# FPGA_IO.net
KiCad netlist of a schematic drawn in Altium Designer
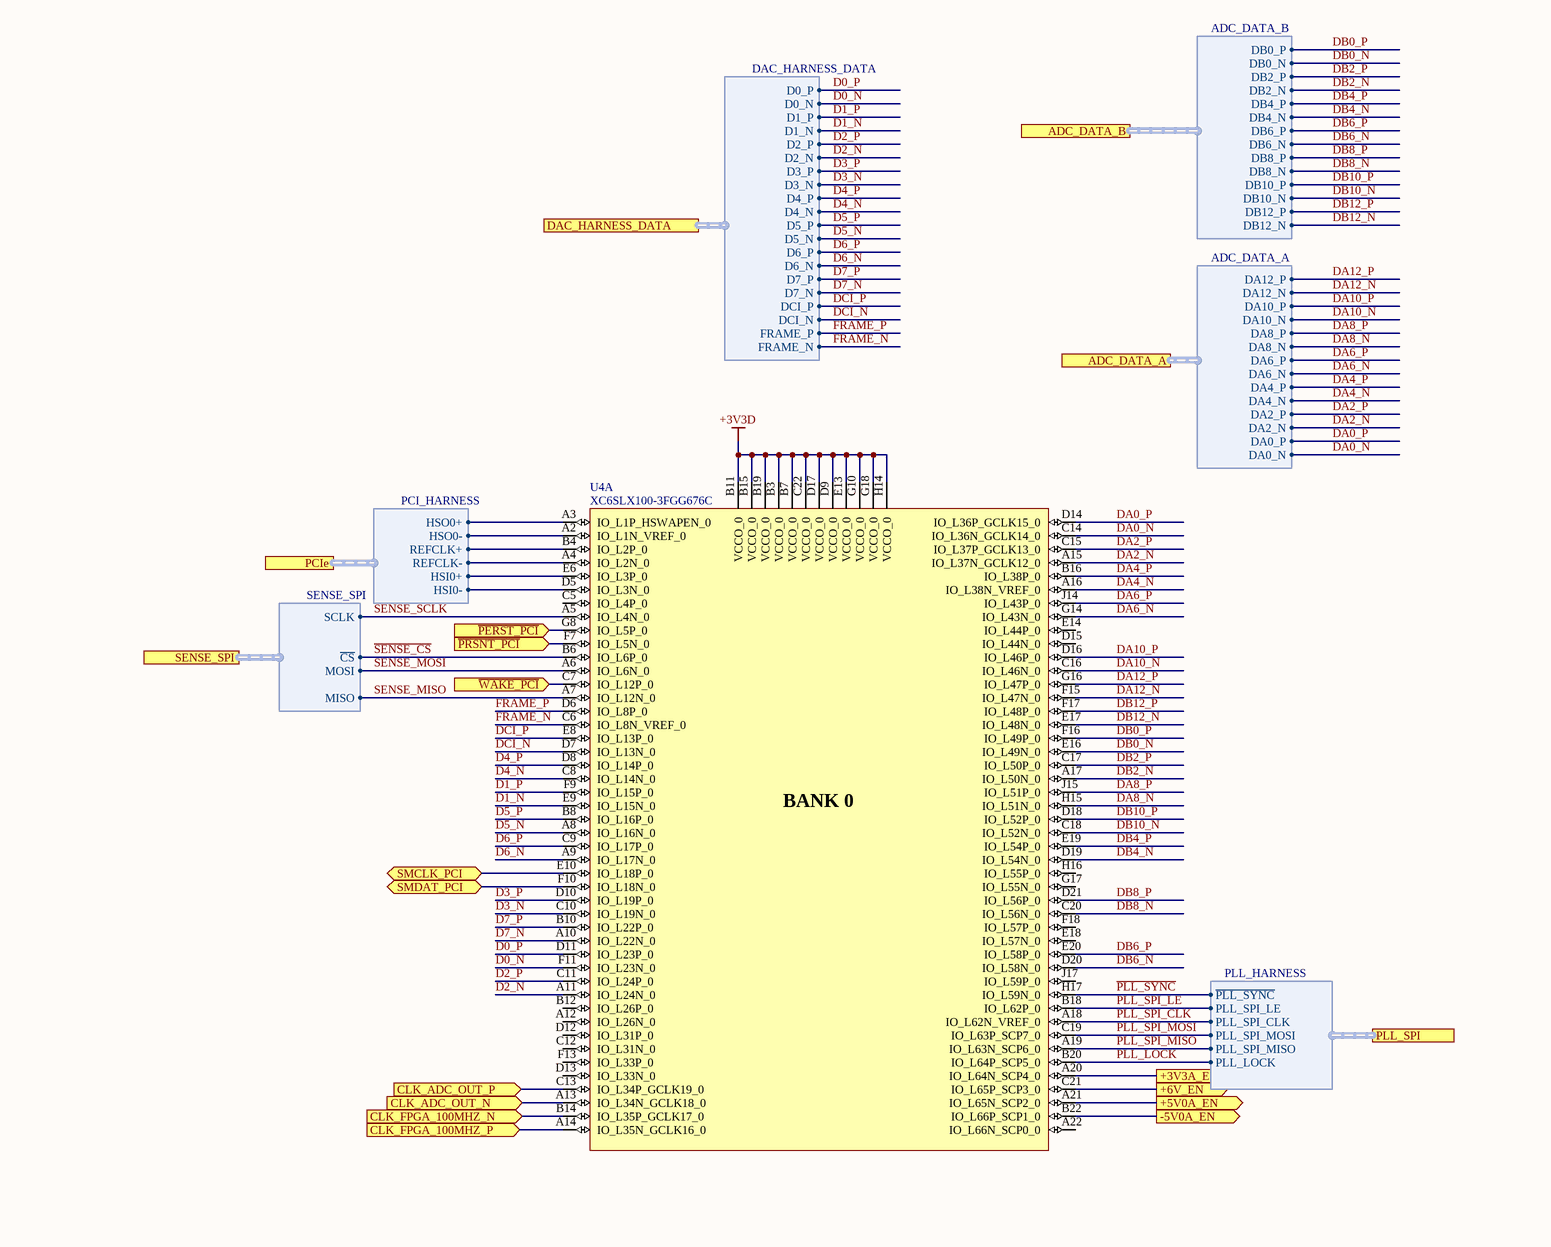
[diagram p0: FPGA_IO.SchDoc, top left]
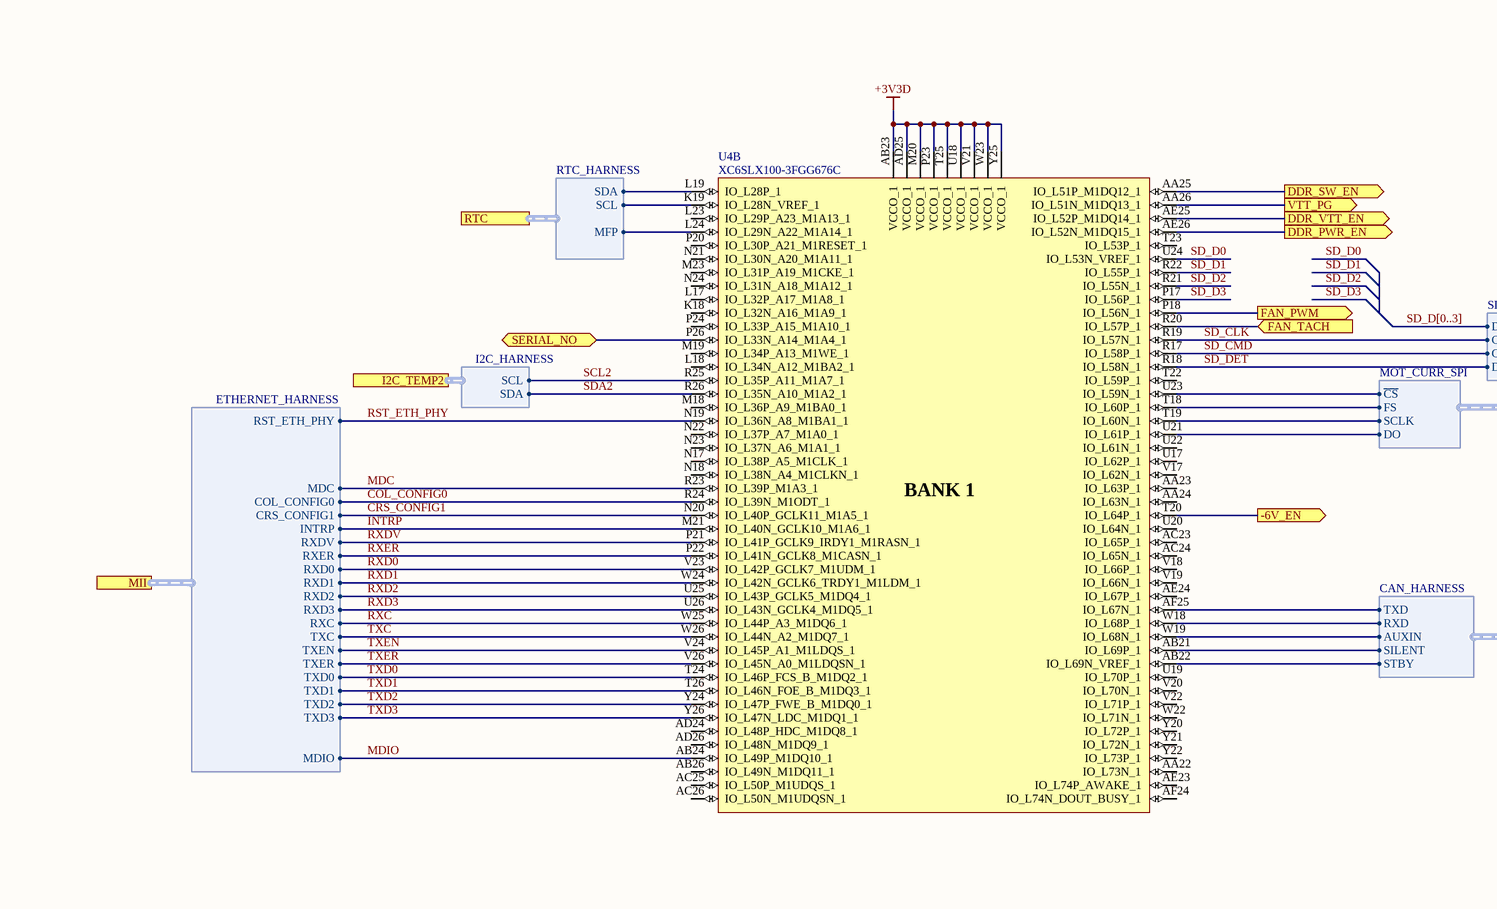
[diagram p1: FPGA_IO.SchDoc, top middle]
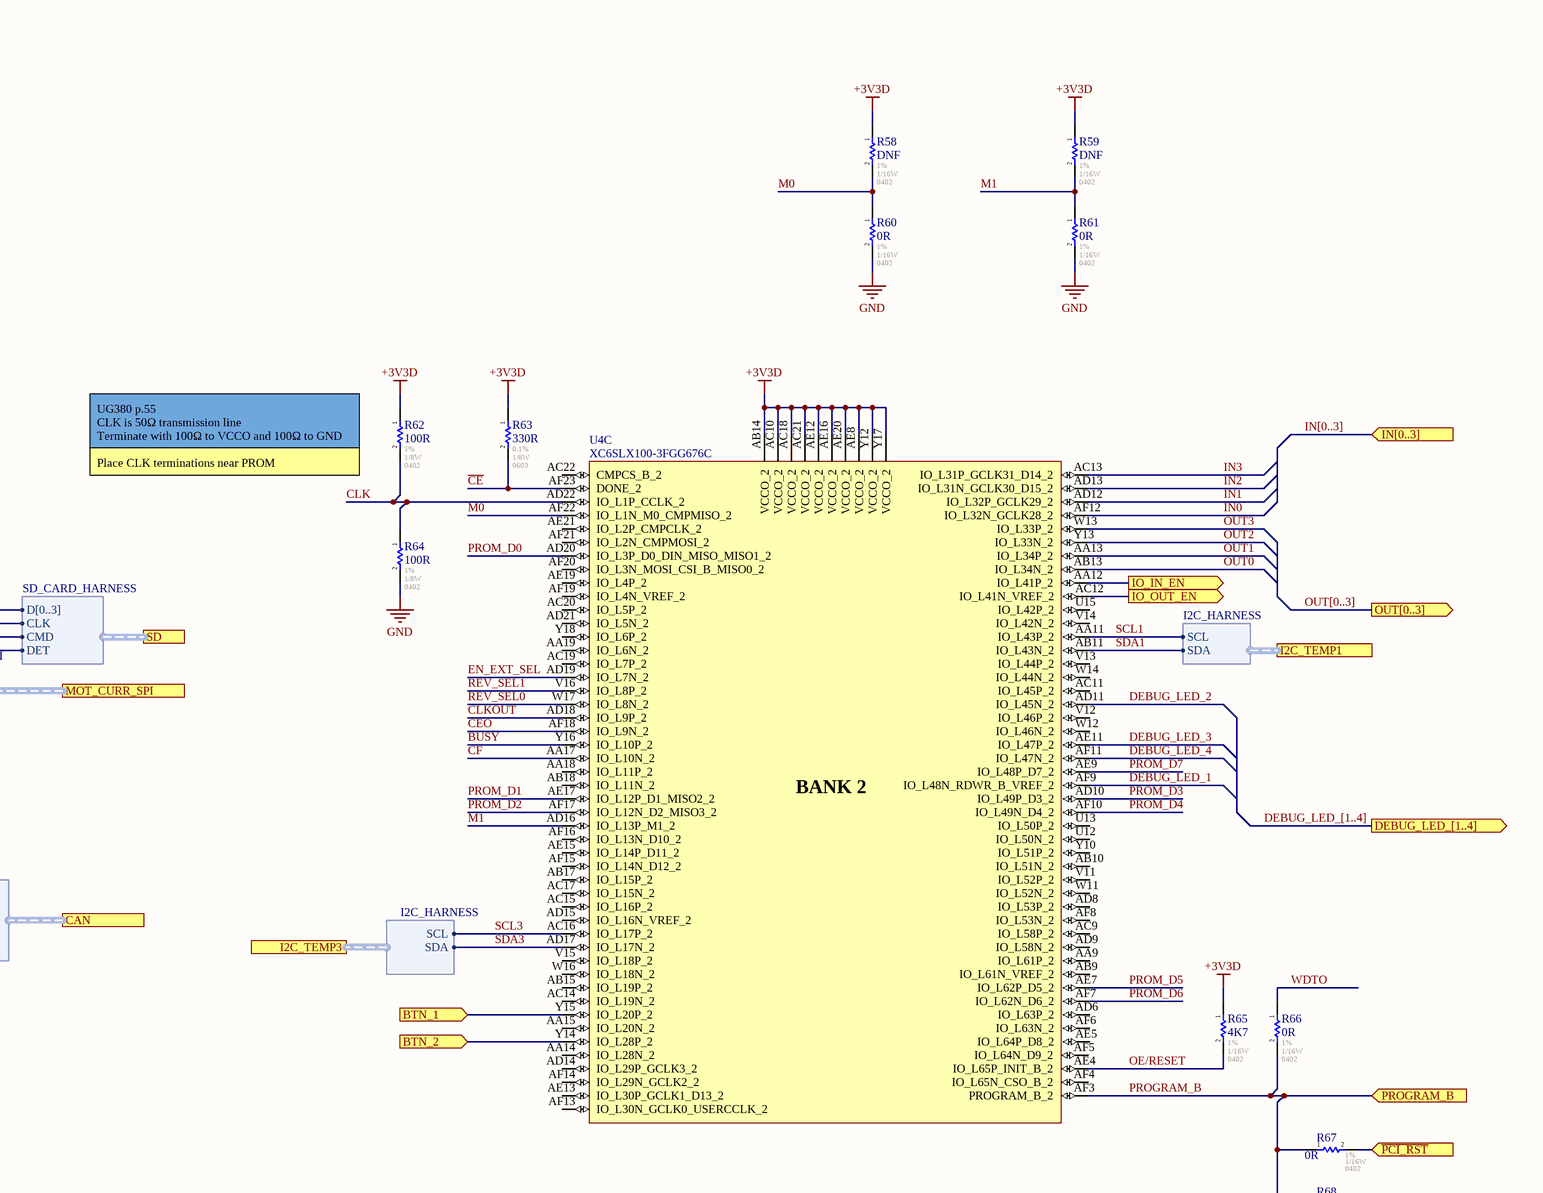
[diagram p2: FPGA_IO.SchDoc, top right]
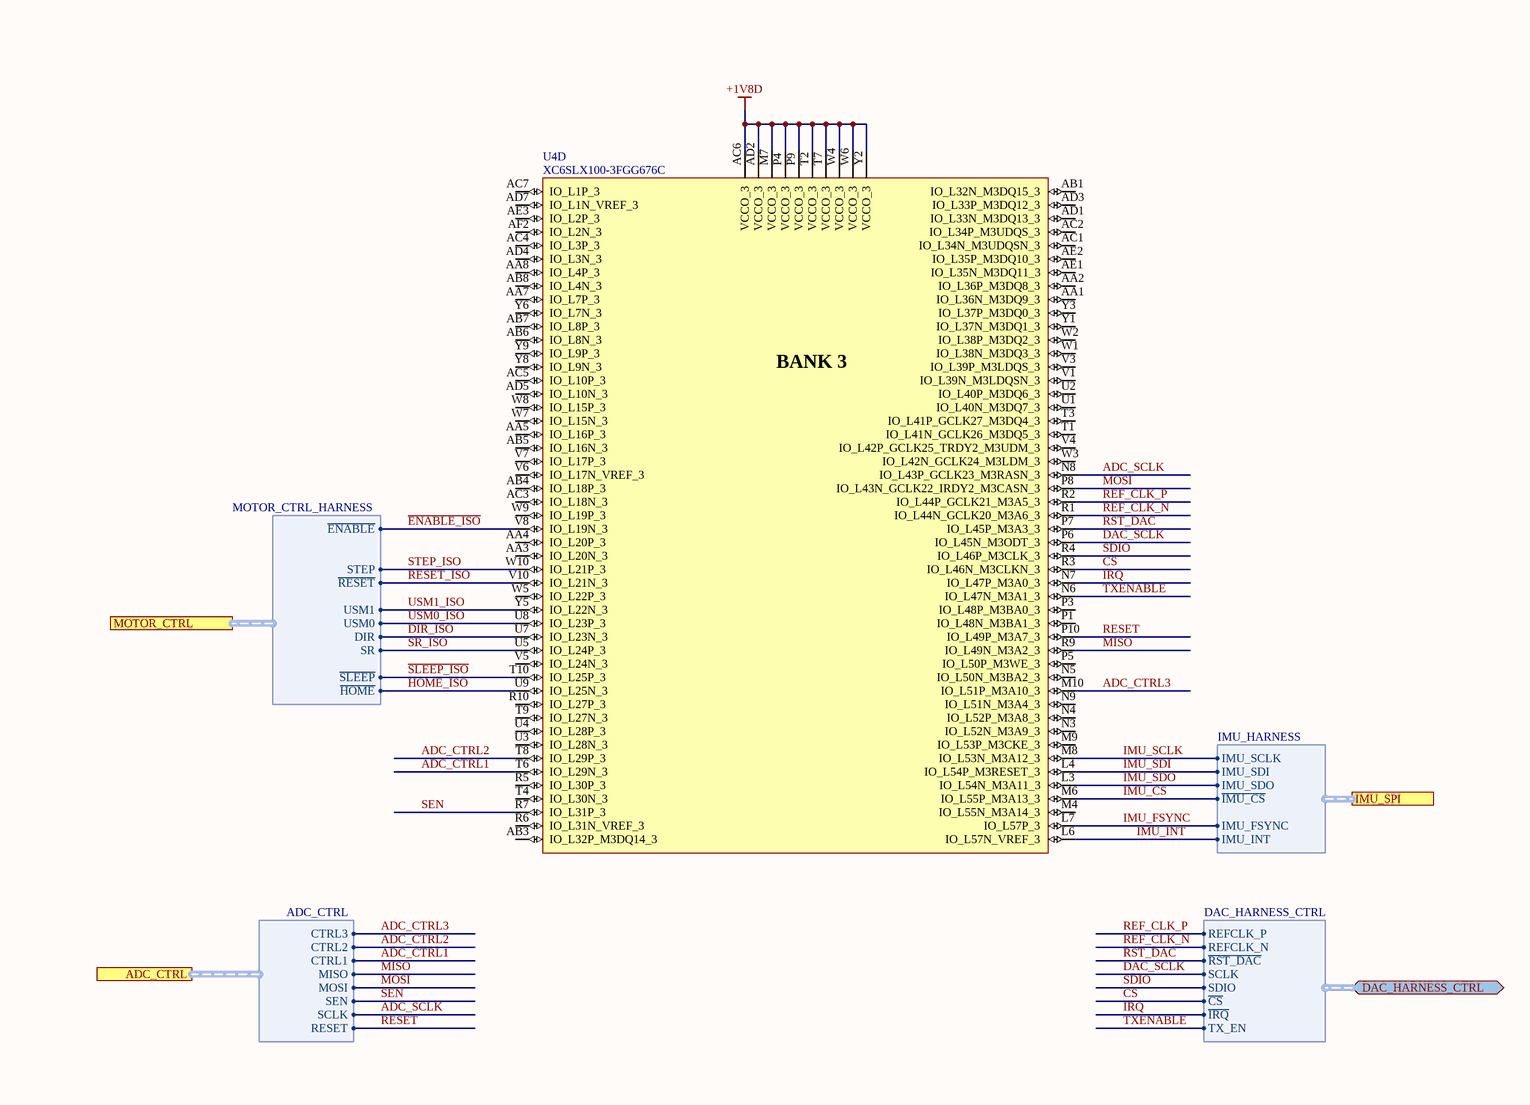
[diagram p3: FPGA_IO.SchDoc, bottom left]
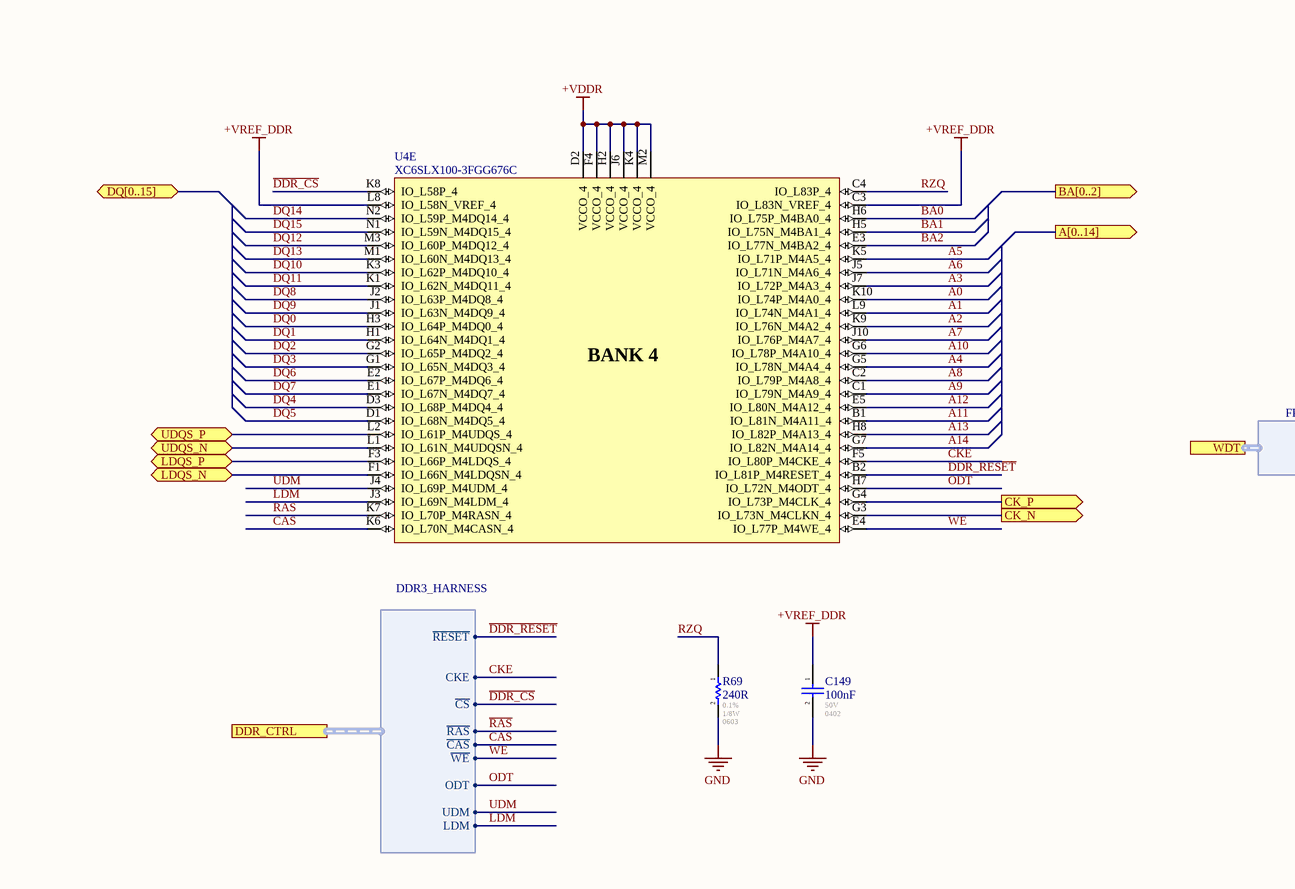
[diagram p4: FPGA_IO.SchDoc, bottom middle]
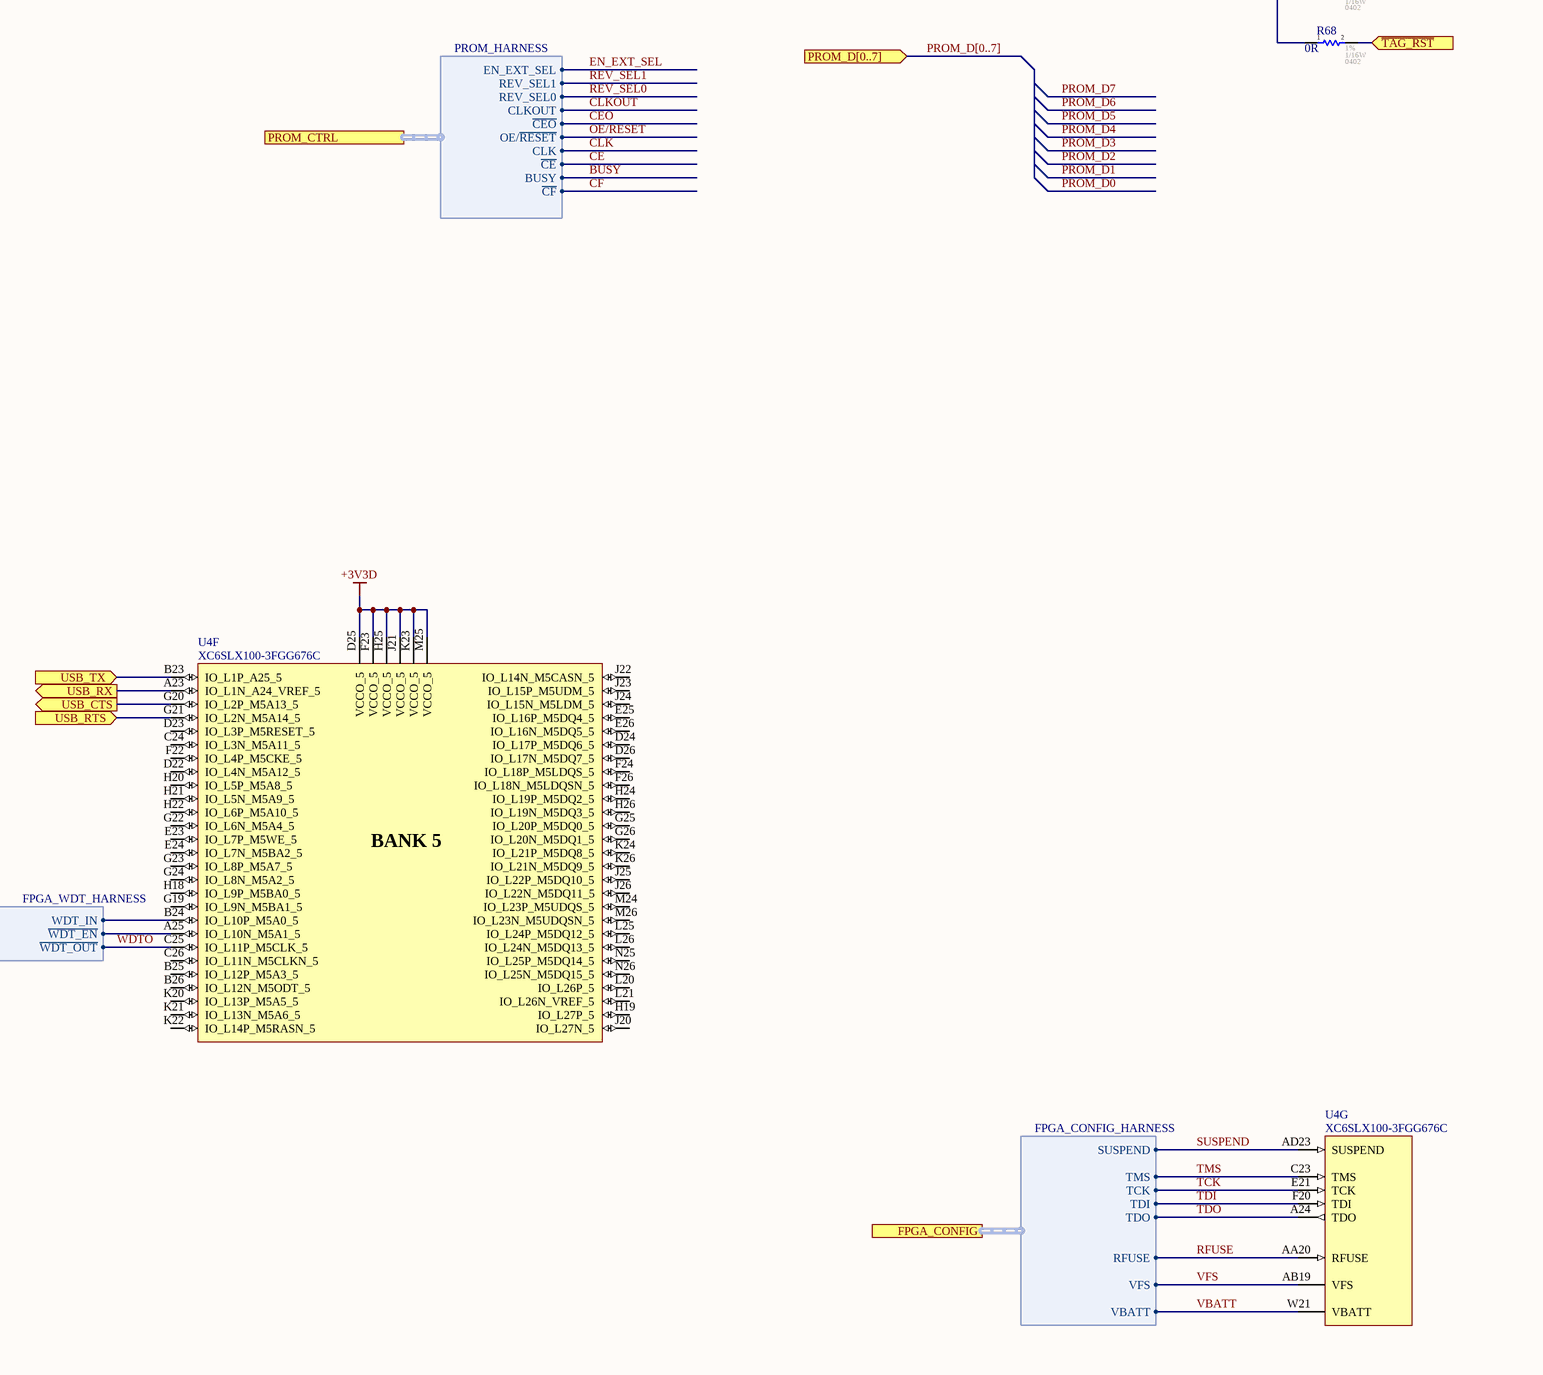
[diagram p5: FPGA_IO.SchDoc, bottom right]

(export (version "E")
  (design (tool "Eeschema 10.0.6"))
  (components
    (comp (ref "C149")
      (value "100nF")
      (footprint "0402")
      (description "GCM155R71H104KE02J\r\n0402 100nF 10% X7R Ceramic Capacitor")
      (fields
        (field (name "MFR") "Murata")
        (field (name "PART#") "GCM155R71H104KE02J")
        (field (name "VOLTAGE - RATED") "50V")
      )
      (libsource (lib "Symbols") (part "CAP_CER"))
    )
    (comp (ref "R58")
      (value "DNF")
      (footprint "RES_0402")
      (fields
        (field (name "TOLERANCE") "1%")
        (field (name "POWER") "1/16W")
        (field (name "PACKAGE / CASE") "0402")
      )
      (libsource (lib "Symbols") (part "RESISTOR"))
    )
    (comp (ref "R59")
      (value "DNF")
      (footprint "RES_0402")
      (fields
        (field (name "TOLERANCE") "1%")
        (field (name "POWER") "1/16W")
        (field (name "PACKAGE / CASE") "0402")
      )
      (libsource (lib "Symbols") (part "RESISTOR"))
    )
    (comp (ref "R60")
      (value "0R")
      (footprint "RES_0402")
      (fields
        (field (name "TOLERANCE") "1%")
        (field (name "POWER") "1/16W")
        (field (name "PACKAGE / CASE") "0402")
      )
      (libsource (lib "Symbols") (part "RESISTOR"))
    )
    (comp (ref "R61")
      (value "0R")
      (footprint "RES_0402")
      (fields
        (field (name "TOLERANCE") "1%")
        (field (name "POWER") "1/16W")
        (field (name "PACKAGE / CASE") "0402")
      )
      (libsource (lib "Symbols") (part "RESISTOR"))
    )
    (comp (ref "R62")
      (value "100R")
      (footprint "RES_0402")
      (fields
        (field (name "TOLERANCE") "1%")
        (field (name "POWER") "1/8W")
        (field (name "PACKAGE / CASE") "0402")
      )
      (libsource (lib "Symbols") (part "RESISTOR"))
    )
    (comp (ref "R63")
      (value "330R")
      (footprint "RES_0603")
      (description "1M 0603 1% 1/16W Resistor")
      (fields
        (field (name "TOLERANCE") "0.1%")
        (field (name "POWER") "1/8W")
        (field (name "PACKAGE / CASE") "0603")
      )
      (libsource (lib "Symbols") (part "RESISTOR"))
    )
    (comp (ref "R64")
      (value "100R")
      (footprint "RES_0402")
      (fields
        (field (name "TOLERANCE") "1%")
        (field (name "POWER") "1/8W")
        (field (name "PACKAGE / CASE") "0402")
      )
      (libsource (lib "Symbols") (part "RESISTOR"))
    )
    (comp (ref "R65")
      (value "4K7")
      (footprint "RES_0402")
      (fields
        (field (name "TOLERANCE") "1%")
        (field (name "POWER") "1/16W")
        (field (name "PACKAGE / CASE") "0402")
      )
      (libsource (lib "Symbols") (part "RESISTOR"))
    )
    (comp (ref "R66")
      (value "0R")
      (footprint "RES_0402")
      (fields
        (field (name "TOLERANCE") "1%")
        (field (name "POWER") "1/16W")
        (field (name "PACKAGE / CASE") "0402")
      )
      (libsource (lib "Symbols") (part "RESISTOR"))
    )
    (comp (ref "R67")
      (value "0R")
      (footprint "RES_0402")
      (fields
        (field (name "TOLERANCE") "1%")
        (field (name "POWER") "1/16W")
        (field (name "PACKAGE / CASE") "0402")
      )
      (libsource (lib "Symbols") (part "RESISTOR"))
    )
    (comp (ref "R68")
      (value "0R")
      (footprint "RES_0402")
      (fields
        (field (name "TOLERANCE") "1%")
        (field (name "POWER") "1/16W")
        (field (name "PACKAGE / CASE") "0402")
      )
      (libsource (lib "Symbols") (part "RESISTOR"))
    )
    (comp (ref "R69")
      (value "240R")
      (footprint "RES_0603")
      (fields
        (field (name "TOLERANCE") "0.1%")
        (field (name "POWER") "1/8W")
        (field (name "PACKAGE / CASE") "0603")
      )
      (libsource (lib "Symbols") (part "RESISTOR"))
    )
    (comp (ref "U4")
      (value "XC6SLX100-3FGG676C")
      (footprint "FPGA_XILINX_FGG676")
      (description "FPGA - XILINX SPARTAN 6 480 I/O - BGA-676")
      (fields
        (field (name "VOLTAGE") "1.14 V ~ 1.26 V")
        (field (name "MFG") "Xilinx")
        (field (name "CREATEDBY") "Jonathan Bouchard")
      )
      (libsource (lib "S7CAS_LIB2023") (part "FPGA_XC6SLX100-3FGG676C"))
    )
  )
  (nets
    (net (code "21") (name "+1V8D") (class "Default")
      (node (ref "U4") (pin "AC6") (pinfunction "VCCO_3_AC6") (pintype "power_in"))
      (node (ref "U4") (pin "AD2") (pinfunction "VCCO_3_AD2") (pintype "power_in"))
      (node (ref "U4") (pin "M7") (pinfunction "VCCO_3_M7") (pintype "power_in"))
      (node (ref "U4") (pin "P4") (pinfunction "VCCO_3_P4") (pintype "power_in"))
      (node (ref "U4") (pin "P9") (pinfunction "VCCO_3_P9") (pintype "power_in"))
      (node (ref "U4") (pin "T2") (pinfunction "VCCO_3_T2") (pintype "power_in"))
      (node (ref "U4") (pin "T7") (pinfunction "VCCO_3_T7") (pintype "power_in"))
      (node (ref "U4") (pin "W4") (pinfunction "VCCO_3_W4") (pintype "power_in"))
      (node (ref "U4") (pin "W6") (pinfunction "VCCO_3_W6") (pintype "power_in"))
      (node (ref "U4") (pin "Y2") (pinfunction "VCCO_3_Y2") (pintype "power_in"))
    )
    (net (code "22") (name "+3V3D") (class "Default")
      (node (ref "R58") (pin "1") (pinfunction "1_1") (pintype "passive"))
      (node (ref "R59") (pin "1") (pinfunction "1_1") (pintype "passive"))
      (node (ref "R62") (pin "1") (pinfunction "1_1") (pintype "passive"))
      (node (ref "R63") (pin "1") (pinfunction "1_1") (pintype "passive"))
      (node (ref "R65") (pin "1") (pinfunction "1_1") (pintype "passive"))
      (node (ref "U4") (pin "AB14") (pinfunction "VCCO_2_AB14") (pintype "power_in"))
      (node (ref "U4") (pin "AB23") (pinfunction "VCCO_1_AB23") (pintype "power_in"))
      (node (ref "U4") (pin "AC10") (pinfunction "VCCO_2_AC10") (pintype "power_in"))
      (node (ref "U4") (pin "AC18") (pinfunction "VCCO_2_AC18") (pintype "power_in"))
      (node (ref "U4") (pin "AC21") (pinfunction "VCCO_2_AC21") (pintype "power_in"))
      (node (ref "U4") (pin "AD25") (pinfunction "VCCO_1_AD25") (pintype "power_in"))
      (node (ref "U4") (pin "AE12") (pinfunction "VCCO_2_AE12") (pintype "power_in"))
      (node (ref "U4") (pin "AE16") (pinfunction "VCCO_2_AE16") (pintype "power_in"))
      (node (ref "U4") (pin "AE20") (pinfunction "VCCO_2_AE20") (pintype "power_in"))
      (node (ref "U4") (pin "AE8") (pinfunction "VCCO_2_AE8") (pintype "power_in"))
      (node (ref "U4") (pin "B11") (pinfunction "VCCO_0_B11") (pintype "power_in"))
      (node (ref "U4") (pin "B15") (pinfunction "VCCO_0_B15") (pintype "power_in"))
      (node (ref "U4") (pin "B19") (pinfunction "VCCO_0_B19") (pintype "power_in"))
      (node (ref "U4") (pin "B3") (pinfunction "VCCO_0_B3") (pintype "power_in"))
      (node (ref "U4") (pin "B7") (pinfunction "VCCO_0_B7") (pintype "power_in"))
      (node (ref "U4") (pin "C22") (pinfunction "VCCO_0_C22") (pintype "power_in"))
      (node (ref "U4") (pin "D17") (pinfunction "VCCO_0_D17") (pintype "power_in"))
      (node (ref "U4") (pin "D25") (pinfunction "VCCO_5_D25") (pintype "power_in"))
      (node (ref "U4") (pin "D9") (pinfunction "VCCO_0_D9") (pintype "power_in"))
      (node (ref "U4") (pin "E13") (pinfunction "VCCO_0_E13") (pintype "power_in"))
      (node (ref "U4") (pin "F23") (pinfunction "VCCO_5_F23") (pintype "power_in"))
      (node (ref "U4") (pin "G10") (pinfunction "VCCO_0_G10") (pintype "power_in"))
      (node (ref "U4") (pin "G18") (pinfunction "VCCO_0_G18") (pintype "power_in"))
      (node (ref "U4") (pin "H14") (pinfunction "VCCO_0_H14") (pintype "power_in"))
      (node (ref "U4") (pin "H25") (pinfunction "VCCO_5_H25") (pintype "power_in"))
      (node (ref "U4") (pin "J21") (pinfunction "VCCO_5_J21") (pintype "power_in"))
      (node (ref "U4") (pin "K23") (pinfunction "VCCO_5_K23") (pintype "power_in"))
      (node (ref "U4") (pin "M20") (pinfunction "VCCO_1_M20") (pintype "power_in"))
      (node (ref "U4") (pin "M25") (pinfunction "VCCO_5_M25") (pintype "power_in"))
      (node (ref "U4") (pin "P23") (pinfunction "VCCO_1_P23") (pintype "power_in"))
      (node (ref "U4") (pin "T25") (pinfunction "VCCO_1_T25") (pintype "power_in"))
      (node (ref "U4") (pin "U18") (pinfunction "VCCO_1_U18") (pintype "power_in"))
      (node (ref "U4") (pin "V21") (pinfunction "VCCO_1_V21") (pintype "power_in"))
      (node (ref "U4") (pin "W23") (pinfunction "VCCO_1_W23") (pintype "power_in"))
      (node (ref "U4") (pin "Y12") (pinfunction "VCCO_2_Y12") (pintype "power_in"))
      (node (ref "U4") (pin "Y17") (pinfunction "VCCO_2_Y17") (pintype "power_in"))
      (node (ref "U4") (pin "Y25") (pinfunction "VCCO_1_Y25") (pintype "power_in"))
    )
    (net (code "23") (name "+VDDR") (class "Default")
      (node (ref "U4") (pin "D2") (pinfunction "VCCO_4_D2") (pintype "power_in"))
      (node (ref "U4") (pin "F4") (pinfunction "VCCO_4_F4") (pintype "power_in"))
      (node (ref "U4") (pin "H2") (pinfunction "VCCO_4_H2") (pintype "power_in"))
      (node (ref "U4") (pin "J6") (pinfunction "VCCO_4_J6") (pintype "power_in"))
      (node (ref "U4") (pin "K4") (pinfunction "VCCO_4_K4") (pintype "power_in"))
      (node (ref "U4") (pin "M2") (pinfunction "VCCO_4_M2") (pintype "power_in"))
    )
    (net (code "24") (name "+VREF_DDR") (class "Default")
      (node (ref "C149") (pin "1") (pinfunction "1_1") (pintype "passive"))
      (node (ref "U4") (pin "C3") (pinfunction "IO_L83N_VREF_4_C3") (pintype "bidirectional"))
      (node (ref "U4") (pin "L8") (pinfunction "IO_L58N_VREF_4_L8") (pintype "bidirectional"))
    )
    (net (code "25") (name "/+3V3A_EN") (class "Default")
      (node (ref "U4") (pin "A20") (pinfunction "IO_L64N_SCP4_0_A20") (pintype "bidirectional"))
    )
    (net (code "26") (name "/+5V0A_EN") (class "Default")
      (node (ref "U4") (pin "A21") (pinfunction "IO_L65N_SCP2_0_A21") (pintype "bidirectional"))
    )
    (net (code "27") (name "/+6V_EN") (class "Default")
      (node (ref "U4") (pin "C21") (pinfunction "IO_L65P_SCP3_0_C21") (pintype "bidirectional"))
    )
    (net (code "28") (name "/-5V0A_EN") (class "Default")
      (node (ref "U4") (pin "B22") (pinfunction "IO_L66P_SCP1_0_B22") (pintype "bidirectional"))
    )
    (net (code "29") (name "/-6V_EN") (class "Default")
      (node (ref "U4") (pin "T20") (pinfunction "IO_L64P_1_T20") (pintype "bidirectional"))
    )
    (net (code "30") (name "/<NO NET>") (class "Default")
      (node (ref "U4") (pin "N7") (pinfunction "IO_L47P_M3A0_3_N7") (pintype "bidirectional"))
    )
    (net (code "31") (name "/A0") (class "Default")
      (node (ref "U4") (pin "K10") (pinfunction "IO_L74P_M4A0_4_K10") (pintype "bidirectional"))
    )
    (net (code "32") (name "/A1") (class "Default")
      (node (ref "U4") (pin "L9") (pinfunction "IO_L74N_M4A1_4_L9") (pintype "bidirectional"))
    )
    (net (code "33") (name "/A2") (class "Default")
      (node (ref "U4") (pin "K9") (pinfunction "IO_L76N_M4A2_4_K9") (pintype "bidirectional"))
    )
    (net (code "34") (name "/A3") (class "Default")
      (node (ref "U4") (pin "J7") (pinfunction "IO_L72P_M4A3_4_J7") (pintype "bidirectional"))
    )
    (net (code "35") (name "/A4") (class "Default")
      (node (ref "U4") (pin "G5") (pinfunction "IO_L78N_M4A4_4_G5") (pintype "bidirectional"))
    )
    (net (code "36") (name "/A5") (class "Default")
      (node (ref "U4") (pin "K5") (pinfunction "IO_L71P_M4A5_4_K5") (pintype "bidirectional"))
    )
    (net (code "37") (name "/A6") (class "Default")
      (node (ref "U4") (pin "J5") (pinfunction "IO_L71N_M4A6_4_J5") (pintype "bidirectional"))
    )
    (net (code "38") (name "/A7") (class "Default")
      (node (ref "U4") (pin "J10") (pinfunction "IO_L76P_M4A7_4_J10") (pintype "bidirectional"))
    )
    (net (code "39") (name "/A8") (class "Default")
      (node (ref "U4") (pin "C2") (pinfunction "IO_L79P_M4A8_4_C2") (pintype "bidirectional"))
    )
    (net (code "40") (name "/A9") (class "Default")
      (node (ref "U4") (pin "C1") (pinfunction "IO_L79N_M4A9_4_C1") (pintype "bidirectional"))
    )
    (net (code "41") (name "/A10") (class "Default")
      (node (ref "U4") (pin "G6") (pinfunction "IO_L78P_M4A10_4_G6") (pintype "bidirectional"))
    )
    (net (code "42") (name "/A11") (class "Default")
      (node (ref "U4") (pin "B1") (pinfunction "IO_L81N_M4A11_4_B1") (pintype "bidirectional"))
    )
    (net (code "43") (name "/A12") (class "Default")
      (node (ref "U4") (pin "E5") (pinfunction "IO_L80N_M4A12_4_E5") (pintype "bidirectional"))
    )
    (net (code "44") (name "/A13") (class "Default")
      (node (ref "U4") (pin "H8") (pinfunction "IO_L82P_M4A13_4_H8") (pintype "bidirectional"))
    )
    (net (code "45") (name "/A14") (class "Default")
      (node (ref "U4") (pin "G7") (pinfunction "IO_L82N_M4A14_4_G7") (pintype "bidirectional"))
    )
    (net (code "46") (name "/ADC_CTRL1") (class "Default")
      (node (ref "U4") (pin "T6") (pinfunction "IO_L29N_3_T6") (pintype "bidirectional"))
    )
    (net (code "47") (name "/ADC_CTRL2") (class "Default")
      (node (ref "U4") (pin "T8") (pinfunction "IO_L29P_3_T8") (pintype "bidirectional"))
    )
    (net (code "48") (name "/ADC_CTRL3") (class "Default")
      (node (ref "U4") (pin "M10") (pinfunction "IO_L51P_M3A10_3_M10") (pintype "bidirectional"))
    )
    (net (code "49") (name "/ADC_SCLK") (class "Default")
      (node (ref "U4") (pin "N8") (pinfunction "IO_L43P_GCLK23_M3RASN_3_N8") (pintype "bidirectional"))
    )
    (net (code "51") (name "/BA0") (class "Default")
      (node (ref "U4") (pin "H6") (pinfunction "IO_L75P_M4BA0_4_H6") (pintype "bidirectional"))
    )
    (net (code "52") (name "/BA1") (class "Default")
      (node (ref "U4") (pin "H5") (pinfunction "IO_L75N_M4BA1_4_H5") (pintype "bidirectional"))
    )
    (net (code "53") (name "/BA2") (class "Default")
      (node (ref "U4") (pin "E3") (pinfunction "IO_L77N_M4BA2_4_E3") (pintype "bidirectional"))
    )
    (net (code "55") (name "/BTN_1") (class "Default")
      (node (ref "U4") (pin "Y15") (pinfunction "IO_L20P_2_Y15") (pintype "bidirectional"))
    )
    (net (code "56") (name "/BTN_2") (class "Default")
      (node (ref "U4") (pin "Y14") (pinfunction "IO_L28P_2_Y14") (pintype "bidirectional"))
    )
    (net (code "57") (name "/BUSY") (class "Default")
      (node (ref "U4") (pin "Y16") (pinfunction "IO_L10P_2_Y16") (pintype "bidirectional"))
    )
    (net (code "58") (name "/CAS") (class "Default")
      (node (ref "U4") (pin "K6") (pinfunction "IO_L70N_M4CASN_4_K6") (pintype "bidirectional"))
    )
    (net (code "59") (name "/CE") (class "Default")
      (node (ref "R63") (pin "2") (pinfunction "2_2") (pintype "passive"))
      (node (ref "U4") (pin "AF23") (pinfunction "DONE_2_AF23") (pintype "bidirectional"))
    )
    (net (code "60") (name "/CEO") (class "Default")
      (node (ref "U4") (pin "AF18") (pinfunction "IO_L9N_2_AF18") (pintype "bidirectional"))
    )
    (net (code "61") (name "/CF") (class "Default")
      (node (ref "U4") (pin "AA17") (pinfunction "IO_L10N_2_AA17") (pintype "bidirectional"))
    )
    (net (code "62") (name "/CKE") (class "Default")
      (node (ref "U4") (pin "F5") (pinfunction "IO_L80P_M4CKE_4_F5") (pintype "bidirectional"))
    )
    (net (code "63") (name "/CK_N") (class "Default")
      (node (ref "U4") (pin "G3") (pinfunction "IO_L73N_M4CLKN_4_G3") (pintype "bidirectional"))
    )
    (net (code "64") (name "/CK_P") (class "Default")
      (node (ref "U4") (pin "G4") (pinfunction "IO_L73P_M4CLK_4_G4") (pintype "bidirectional"))
    )
    (net (code "65") (name "/CLK") (class "Default")
      (node (ref "R62") (pin "2") (pinfunction "2_2") (pintype "passive"))
      (node (ref "R64") (pin "1") (pinfunction "1_1") (pintype "passive"))
      (node (ref "U4") (pin "AD22") (pinfunction "IO_L1P_CCLK_2_AD22") (pintype "bidirectional"))
    )
    (net (code "66") (name "/CLKOUT") (class "Default")
      (node (ref "U4") (pin "AD18") (pinfunction "IO_L9P_2_AD18") (pintype "bidirectional"))
    )
    (net (code "67") (name "/CLK_ADC_OUT_N") (class "Default")
      (node (ref "U4") (pin "A13") (pinfunction "IO_L34N_GCLK18_0_A13") (pintype "bidirectional"))
    )
    (net (code "68") (name "/CLK_ADC_OUT_P") (class "Default")
      (node (ref "U4") (pin "C13") (pinfunction "IO_L34P_GCLK19_0_C13") (pintype "bidirectional"))
    )
    (net (code "69") (name "/CLK_FPGA_100MHZ_N") (class "Default")
      (node (ref "U4") (pin "B14") (pinfunction "IO_L35P_GCLK17_0_B14") (pintype "bidirectional"))
    )
    (net (code "70") (name "/CLK_FPGA_100MHZ_P") (class "Default")
      (node (ref "U4") (pin "A14") (pinfunction "IO_L35N_GCLK16_0_A14") (pintype "bidirectional"))
    )
    (net (code "71") (name "/COL_CONFIG0") (class "Default")
      (node (ref "U4") (pin "R24") (pinfunction "IO_L39N_M1ODT_1_R24") (pintype "bidirectional"))
    )
    (net (code "72") (name "/CRS_CONFIG1") (class "Default")
      (node (ref "U4") (pin "N20") (pinfunction "IO_L40P_GCLK11_M1A5_1_N20") (pintype "bidirectional"))
    )
    (net (code "73") (name "/CS") (class "Default")
      (node (ref "U4") (pin "R3") (pinfunction "IO_L46N_M3CLKN_3_R3") (pintype "bidirectional"))
    )
    (net (code "74") (name "/D0_N") (class "Default")
      (node (ref "U4") (pin "F11") (pinfunction "IO_L23N_0_F11") (pintype "bidirectional"))
    )
    (net (code "75") (name "/D0_P") (class "Default")
      (node (ref "U4") (pin "D11") (pinfunction "IO_L23P_0_D11") (pintype "bidirectional"))
    )
    (net (code "76") (name "/D1_N") (class "Default")
      (node (ref "U4") (pin "E9") (pinfunction "IO_L15N_0_E9") (pintype "bidirectional"))
    )
    (net (code "77") (name "/D1_P") (class "Default")
      (node (ref "U4") (pin "F9") (pinfunction "IO_L15P_0_F9") (pintype "bidirectional"))
    )
    (net (code "78") (name "/D2_N") (class "Default")
      (node (ref "U4") (pin "A11") (pinfunction "IO_L24N_0_A11") (pintype "bidirectional"))
    )
    (net (code "79") (name "/D2_P") (class "Default")
      (node (ref "U4") (pin "C11") (pinfunction "IO_L24P_0_C11") (pintype "bidirectional"))
    )
    (net (code "80") (name "/D3_N") (class "Default")
      (node (ref "U4") (pin "C10") (pinfunction "IO_L19N_0_C10") (pintype "bidirectional"))
    )
    (net (code "81") (name "/D3_P") (class "Default")
      (node (ref "U4") (pin "D10") (pinfunction "IO_L19P_0_D10") (pintype "bidirectional"))
    )
    (net (code "82") (name "/D4_N") (class "Default")
      (node (ref "U4") (pin "C8") (pinfunction "IO_L14N_0_C8") (pintype "bidirectional"))
    )
    (net (code "83") (name "/D4_P") (class "Default")
      (node (ref "U4") (pin "D8") (pinfunction "IO_L14P_0_D8") (pintype "bidirectional"))
    )
    (net (code "84") (name "/D5_N") (class "Default")
      (node (ref "U4") (pin "A8") (pinfunction "IO_L16N_0_A8") (pintype "bidirectional"))
    )
    (net (code "85") (name "/D5_P") (class "Default")
      (node (ref "U4") (pin "B8") (pinfunction "IO_L16P_0_B8") (pintype "bidirectional"))
    )
    (net (code "86") (name "/D6_N") (class "Default")
      (node (ref "U4") (pin "A9") (pinfunction "IO_L17N_0_A9") (pintype "bidirectional"))
    )
    (net (code "87") (name "/D6_P") (class "Default")
      (node (ref "U4") (pin "C9") (pinfunction "IO_L17P_0_C9") (pintype "bidirectional"))
    )
    (net (code "88") (name "/D7_N") (class "Default")
      (node (ref "U4") (pin "A10") (pinfunction "IO_L22N_0_A10") (pintype "bidirectional"))
    )
    (net (code "89") (name "/D7_P") (class "Default")
      (node (ref "U4") (pin "B10") (pinfunction "IO_L22P_0_B10") (pintype "bidirectional"))
    )
    (net (code "90") (name "/DA0_N") (class "Default")
      (node (ref "U4") (pin "C14") (pinfunction "IO_L36N_GCLK14_0_C14") (pintype "bidirectional"))
    )
    (net (code "91") (name "/DA0_P") (class "Default")
      (node (ref "U4") (pin "D14") (pinfunction "IO_L36P_GCLK15_0_D14") (pintype "bidirectional"))
    )
    (net (code "92") (name "/DA2_N") (class "Default")
      (node (ref "U4") (pin "A15") (pinfunction "IO_L37N_GCLK12_0_A15") (pintype "bidirectional"))
    )
    (net (code "93") (name "/DA2_P") (class "Default")
      (node (ref "U4") (pin "C15") (pinfunction "IO_L37P_GCLK13_0_C15") (pintype "bidirectional"))
    )
    (net (code "94") (name "/DA4_N") (class "Default")
      (node (ref "U4") (pin "A16") (pinfunction "IO_L38N_VREF_0_A16") (pintype "bidirectional"))
    )
    (net (code "95") (name "/DA4_P") (class "Default")
      (node (ref "U4") (pin "B16") (pinfunction "IO_L38P_0_B16") (pintype "bidirectional"))
    )
    (net (code "96") (name "/DA6_N") (class "Default")
      (node (ref "U4") (pin "G14") (pinfunction "IO_L43N_0_G14") (pintype "bidirectional"))
    )
    (net (code "97") (name "/DA6_P") (class "Default")
      (node (ref "U4") (pin "J14") (pinfunction "IO_L43P_0_J14") (pintype "bidirectional"))
    )
    (net (code "98") (name "/DA8_N") (class "Default")
      (node (ref "U4") (pin "H15") (pinfunction "IO_L51N_0_H15") (pintype "bidirectional"))
    )
    (net (code "99") (name "/DA8_P") (class "Default")
      (node (ref "U4") (pin "J15") (pinfunction "IO_L51P_0_J15") (pintype "bidirectional"))
    )
    (net (code "100") (name "/DA10_N") (class "Default")
      (node (ref "U4") (pin "C16") (pinfunction "IO_L46N_0_C16") (pintype "bidirectional"))
    )
    (net (code "101") (name "/DA10_P") (class "Default")
      (node (ref "U4") (pin "D16") (pinfunction "IO_L46P_0_D16") (pintype "bidirectional"))
    )
    (net (code "102") (name "/DA12_N") (class "Default")
      (node (ref "U4") (pin "F15") (pinfunction "IO_L47N_0_F15") (pintype "bidirectional"))
    )
    (net (code "103") (name "/DA12_P") (class "Default")
      (node (ref "U4") (pin "G16") (pinfunction "IO_L47P_0_G16") (pintype "bidirectional"))
    )
    (net (code "104") (name "/DAC_SCLK") (class "Default")
      (node (ref "U4") (pin "P6") (pinfunction "IO_L45N_M3ODT_3_P6") (pintype "bidirectional"))
    )
    (net (code "105") (name "/DB0_N") (class "Default")
      (node (ref "U4") (pin "E16") (pinfunction "IO_L49N_0_E16") (pintype "bidirectional"))
    )
    (net (code "106") (name "/DB0_P") (class "Default")
      (node (ref "U4") (pin "F16") (pinfunction "IO_L49P_0_F16") (pintype "bidirectional"))
    )
    (net (code "107") (name "/DB2_N") (class "Default")
      (node (ref "U4") (pin "A17") (pinfunction "IO_L50N_0_A17") (pintype "bidirectional"))
    )
    (net (code "108") (name "/DB2_P") (class "Default")
      (node (ref "U4") (pin "C17") (pinfunction "IO_L50P_0_C17") (pintype "bidirectional"))
    )
    (net (code "109") (name "/DB4_N") (class "Default")
      (node (ref "U4") (pin "D19") (pinfunction "IO_L54N_0_D19") (pintype "bidirectional"))
    )
    (net (code "110") (name "/DB4_P") (class "Default")
      (node (ref "U4") (pin "E19") (pinfunction "IO_L54P_0_E19") (pintype "bidirectional"))
    )
    (net (code "111") (name "/DB6_N") (class "Default")
      (node (ref "U4") (pin "D20") (pinfunction "IO_L58N_0_D20") (pintype "bidirectional"))
    )
    (net (code "112") (name "/DB6_P") (class "Default")
      (node (ref "U4") (pin "E20") (pinfunction "IO_L58P_0_E20") (pintype "bidirectional"))
    )
    (net (code "113") (name "/DB8_N") (class "Default")
      (node (ref "U4") (pin "C20") (pinfunction "IO_L56N_0_C20") (pintype "bidirectional"))
    )
    (net (code "114") (name "/DB8_P") (class "Default")
      (node (ref "U4") (pin "D21") (pinfunction "IO_L56P_0_D21") (pintype "bidirectional"))
    )
    (net (code "115") (name "/DB10_N") (class "Default")
      (node (ref "U4") (pin "C18") (pinfunction "IO_L52N_0_C18") (pintype "bidirectional"))
    )
    (net (code "116") (name "/DB10_P") (class "Default")
      (node (ref "U4") (pin "D18") (pinfunction "IO_L52P_0_D18") (pintype "bidirectional"))
    )
    (net (code "117") (name "/DB12_N") (class "Default")
      (node (ref "U4") (pin "E17") (pinfunction "IO_L48N_0_E17") (pintype "bidirectional"))
    )
    (net (code "118") (name "/DB12_P") (class "Default")
      (node (ref "U4") (pin "F17") (pinfunction "IO_L48P_0_F17") (pintype "bidirectional"))
    )
    (net (code "119") (name "/DCI_N") (class "Default")
      (node (ref "U4") (pin "D7") (pinfunction "IO_L13N_0_D7") (pintype "bidirectional"))
    )
    (net (code "120") (name "/DCI_P") (class "Default")
      (node (ref "U4") (pin "E8") (pinfunction "IO_L13P_0_E8") (pintype "bidirectional"))
    )
    (net (code "121") (name "/DDR_CS") (class "Default")
      (node (ref "U4") (pin "K8") (pinfunction "IO_L58P_4_K8") (pintype "bidirectional"))
    )
    (net (code "122") (name "/DDR_PWR_EN") (class "Default")
      (node (ref "U4") (pin "AE26") (pinfunction "IO_L52N_M1DQ15_1_AE26") (pintype "bidirectional"))
    )
    (net (code "123") (name "/DDR_RESET") (class "Default")
      (node (ref "U4") (pin "B2") (pinfunction "IO_L81P_M4RESET_4_B2") (pintype "bidirectional"))
    )
    (net (code "124") (name "/DDR_SW_EN") (class "Default")
      (node (ref "U4") (pin "AA25") (pinfunction "IO_L51P_M1DQ12_1_AA25") (pintype "bidirectional"))
    )
    (net (code "125") (name "/DDR_VTT_EN") (class "Default")
      (node (ref "U4") (pin "AE25") (pinfunction "IO_L52P_M1DQ14_1_AE25") (pintype "bidirectional"))
    )
    (net (code "126") (name "/DEBUG_LED_1") (class "Default")
      (node (ref "U4") (pin "AF9") (pinfunction "IO_L48N_RDWR_B_VREF_2_AF9") (pintype "bidirectional"))
    )
    (net (code "127") (name "/DEBUG_LED_2") (class "Default")
      (node (ref "U4") (pin "AD11") (pinfunction "IO_L45N_2_AD11") (pintype "bidirectional"))
    )
    (net (code "128") (name "/DEBUG_LED_3") (class "Default")
      (node (ref "U4") (pin "AE11") (pinfunction "IO_L47P_2_AE11") (pintype "bidirectional"))
    )
    (net (code "129") (name "/DEBUG_LED_4") (class "Default")
      (node (ref "U4") (pin "AF11") (pinfunction "IO_L47N_2_AF11") (pintype "bidirectional"))
    )
    (net (code "131") (name "/DIR_ISO") (class "Default")
      (node (ref "U4") (pin "U7") (pinfunction "IO_L23N_3_U7") (pintype "bidirectional"))
    )
    (net (code "132") (name "/DQ0") (class "Default")
      (node (ref "U4") (pin "H3") (pinfunction "IO_L64P_M4DQ0_4_H3") (pintype "bidirectional"))
    )
    (net (code "133") (name "/DQ1") (class "Default")
      (node (ref "U4") (pin "H1") (pinfunction "IO_L64N_M4DQ1_4_H1") (pintype "bidirectional"))
    )
    (net (code "134") (name "/DQ2") (class "Default")
      (node (ref "U4") (pin "G2") (pinfunction "IO_L65P_M4DQ2_4_G2") (pintype "bidirectional"))
    )
    (net (code "135") (name "/DQ3") (class "Default")
      (node (ref "U4") (pin "G1") (pinfunction "IO_L65N_M4DQ3_4_G1") (pintype "bidirectional"))
    )
    (net (code "136") (name "/DQ4") (class "Default")
      (node (ref "U4") (pin "D3") (pinfunction "IO_L68P_M4DQ4_4_D3") (pintype "bidirectional"))
    )
    (net (code "137") (name "/DQ5") (class "Default")
      (node (ref "U4") (pin "D1") (pinfunction "IO_L68N_M4DQ5_4_D1") (pintype "bidirectional"))
    )
    (net (code "138") (name "/DQ6") (class "Default")
      (node (ref "U4") (pin "E2") (pinfunction "IO_L67P_M4DQ6_4_E2") (pintype "bidirectional"))
    )
    (net (code "139") (name "/DQ7") (class "Default")
      (node (ref "U4") (pin "E1") (pinfunction "IO_L67N_M4DQ7_4_E1") (pintype "bidirectional"))
    )
    (net (code "140") (name "/DQ8") (class "Default")
      (node (ref "U4") (pin "J2") (pinfunction "IO_L63P_M4DQ8_4_J2") (pintype "bidirectional"))
    )
    (net (code "141") (name "/DQ9") (class "Default")
      (node (ref "U4") (pin "J1") (pinfunction "IO_L63N_M4DQ9_4_J1") (pintype "bidirectional"))
    )
    (net (code "142") (name "/DQ10") (class "Default")
      (node (ref "U4") (pin "K3") (pinfunction "IO_L62P_M4DQ10_4_K3") (pintype "bidirectional"))
    )
    (net (code "143") (name "/DQ11") (class "Default")
      (node (ref "U4") (pin "K1") (pinfunction "IO_L62N_M4DQ11_4_K1") (pintype "bidirectional"))
    )
    (net (code "144") (name "/DQ12") (class "Default")
      (node (ref "U4") (pin "M3") (pinfunction "IO_L60P_M4DQ12_4_M3") (pintype "bidirectional"))
    )
    (net (code "145") (name "/DQ13") (class "Default")
      (node (ref "U4") (pin "M1") (pinfunction "IO_L60N_M4DQ13_4_M1") (pintype "bidirectional"))
    )
    (net (code "146") (name "/DQ14") (class "Default")
      (node (ref "U4") (pin "N2") (pinfunction "IO_L59P_M4DQ14_4_N2") (pintype "bidirectional"))
    )
    (net (code "147") (name "/DQ15") (class "Default")
      (node (ref "U4") (pin "N1") (pinfunction "IO_L59N_M4DQ15_4_N1") (pintype "bidirectional"))
    )
    (net (code "149") (name "/ENABLE_ISO") (class "Default")
      (node (ref "U4") (pin "V8") (pinfunction "IO_L19N_3_V8") (pintype "bidirectional"))
    )
    (net (code "150") (name "/EN_EXT_SEL") (class "Default")
      (node (ref "U4") (pin "AD19") (pinfunction "IO_L7N_2_AD19") (pintype "bidirectional"))
    )
    (net (code "151") (name "/FAN_PWM") (class "Default")
      (node (ref "U4") (pin "P18") (pinfunction "IO_L56N_1_P18") (pintype "bidirectional"))
    )
    (net (code "152") (name "/FAN_TACH") (class "Default")
      (node (ref "U4") (pin "R20") (pinfunction "IO_L57P_1_R20") (pintype "bidirectional"))
    )
    (net (code "153") (name "/FRAME_N") (class "Default")
      (node (ref "U4") (pin "C6") (pinfunction "IO_L8N_VREF_0_C6") (pintype "bidirectional"))
    )
    (net (code "154") (name "/FRAME_P") (class "Default")
      (node (ref "U4") (pin "D6") (pinfunction "IO_L8P_0_D6") (pintype "bidirectional"))
    )
    (net (code "155") (name "/HOME_ISO") (class "Default")
      (node (ref "U4") (pin "U9") (pinfunction "IO_L25N_3_U9") (pintype "bidirectional"))
    )
    (net (code "156") (name "/IMU_CS") (class "Default")
      (node (ref "U4") (pin "M6") (pinfunction "IO_L55P_M3A13_3_M6") (pintype "bidirectional"))
    )
    (net (code "157") (name "/IMU_FSYNC") (class "Default")
      (node (ref "U4") (pin "L7") (pinfunction "IO_L57P_3_L7") (pintype "bidirectional"))
    )
    (net (code "158") (name "/IMU_INT") (class "Default")
      (node (ref "U4") (pin "L6") (pinfunction "IO_L57N_VREF_3_L6") (pintype "bidirectional"))
    )
    (net (code "159") (name "/IMU_SCLK") (class "Default")
      (node (ref "U4") (pin "M8") (pinfunction "IO_L53N_M3A12_3_M8") (pintype "bidirectional"))
    )
    (net (code "160") (name "/IMU_SDI") (class "Default")
      (node (ref "U4") (pin "L4") (pinfunction "IO_L54P_M3RESET_3_L4") (pintype "bidirectional"))
    )
    (net (code "161") (name "/IMU_SDO") (class "Default")
      (node (ref "U4") (pin "L3") (pinfunction "IO_L54N_M3A11_3_L3") (pintype "bidirectional"))
    )
    (net (code "162") (name "/IN0") (class "Default")
      (node (ref "U4") (pin "AF12") (pinfunction "IO_L32N_GCLK28_2_AF12") (pintype "bidirectional"))
    )
    (net (code "163") (name "/IN1") (class "Default")
      (node (ref "U4") (pin "AD12") (pinfunction "IO_L32P_GCLK29_2_AD12") (pintype "bidirectional"))
    )
    (net (code "164") (name "/IN2") (class "Default")
      (node (ref "U4") (pin "AD13") (pinfunction "IO_L31N_GCLK30_D15_2_AD13") (pintype "bidirectional"))
    )
    (net (code "165") (name "/IN3") (class "Default")
      (node (ref "U4") (pin "AC13") (pinfunction "IO_L31P_GCLK31_D14_2_AC13") (pintype "bidirectional"))
    )
    (net (code "166") (name "/INTRP") (class "Default")
      (node (ref "U4") (pin "M21") (pinfunction "IO_L40N_GCLK10_M1A6_1_M21") (pintype "bidirectional"))
    )
    (net (code "168") (name "/IO_IN_EN") (class "Default")
      (node (ref "U4") (pin "AA12") (pinfunction "IO_L41P_2_AA12") (pintype "bidirectional"))
    )
    (net (code "169") (name "/IO_OUT_EN") (class "Default")
      (node (ref "U4") (pin "AC12") (pinfunction "IO_L41N_VREF_2_AC12") (pintype "bidirectional"))
    )
    (net (code "170") (name "/LDM") (class "Default")
      (node (ref "U4") (pin "J3") (pinfunction "IO_L69N_M4LDM_4_J3") (pintype "bidirectional"))
    )
    (net (code "171") (name "/LDQS_N") (class "Default")
      (node (ref "U4") (pin "F1") (pinfunction "IO_L66N_M4LDQSN_4_F1") (pintype "bidirectional"))
    )
    (net (code "172") (name "/LDQS_P") (class "Default")
      (node (ref "U4") (pin "F3") (pinfunction "IO_L66P_M4LDQS_4_F3") (pintype "bidirectional"))
    )
    (net (code "173") (name "/M0") (class "Default")
      (node (ref "R58") (pin "2") (pinfunction "2_2") (pintype "passive"))
      (node (ref "R60") (pin "1") (pinfunction "1_1") (pintype "passive"))
      (node (ref "U4") (pin "AF22") (pinfunction "IO_L1N_M0_CMPMISO_2_AF22") (pintype "bidirectional"))
    )
    (net (code "174") (name "/M1") (class "Default")
      (node (ref "R59") (pin "2") (pinfunction "2_2") (pintype "passive"))
      (node (ref "R61") (pin "1") (pinfunction "1_1") (pintype "passive"))
      (node (ref "U4") (pin "AD16") (pinfunction "IO_L13P_M1_2_AD16") (pintype "bidirectional"))
    )
    (net (code "175") (name "/MDC") (class "Default")
      (node (ref "U4") (pin "R23") (pinfunction "IO_L39P_M1A3_1_R23") (pintype "bidirectional"))
    )
    (net (code "176") (name "/MDIO") (class "Default")
      (node (ref "U4") (pin "AB24") (pinfunction "IO_L49P_M1DQ10_1_AB24") (pintype "bidirectional"))
    )
    (net (code "177") (name "/MISO") (class "Default")
      (node (ref "U4") (pin "R9") (pinfunction "IO_L49N_M3A2_3_R9") (pintype "bidirectional"))
    )
    (net (code "178") (name "/MOSI") (class "Default")
      (node (ref "U4") (pin "P8") (pinfunction "IO_L43N_GCLK22_IRDY2_M3CASN_3_P8") (pintype "bidirectional"))
    )
    (net (code "179") (name "/ODT") (class "Default")
      (node (ref "U4") (pin "H7") (pinfunction "IO_L72N_M4ODT_4_H7") (pintype "bidirectional"))
    )
    (net (code "180") (name "/OE{slash}RESET") (class "Default")
      (node (ref "R65") (pin "2") (pinfunction "2_2") (pintype "passive"))
      (node (ref "U4") (pin "AE4") (pinfunction "IO_L65P_INIT_B_2_AE4") (pintype "bidirectional"))
    )
    (net (code "181") (name "/OUT0") (class "Default")
      (node (ref "U4") (pin "AB13") (pinfunction "IO_L34N_2_AB13") (pintype "bidirectional"))
    )
    (net (code "182") (name "/OUT1") (class "Default")
      (node (ref "U4") (pin "AA13") (pinfunction "IO_L34P_2_AA13") (pintype "bidirectional"))
    )
    (net (code "183") (name "/OUT2") (class "Default")
      (node (ref "U4") (pin "Y13") (pinfunction "IO_L33N_2_Y13") (pintype "bidirectional"))
    )
    (net (code "184") (name "/OUT3") (class "Default")
      (node (ref "U4") (pin "W13") (pinfunction "IO_L33P_2_W13") (pintype "bidirectional"))
    )
    (net (code "186") (name "/PCI_RST") (class "Default")
      (node (ref "R67") (pin "2") (pinfunction "2_2") (pintype "passive"))
    )
    (net (code "187") (name "/PERST_PCI") (class "Default")
      (node (ref "U4") (pin "G8") (pinfunction "IO_L5P_0_G8") (pintype "bidirectional"))
    )
    (net (code "188") (name "/PLL_LOCK") (class "Default")
      (node (ref "U4") (pin "B20") (pinfunction "IO_L64P_SCP5_0_B20") (pintype "bidirectional"))
    )
    (net (code "189") (name "/PLL_SPI_CLK") (class "Default")
      (node (ref "U4") (pin "A18") (pinfunction "IO_L62N_VREF_0_A18") (pintype "bidirectional"))
    )
    (net (code "190") (name "/PLL_SPI_LE") (class "Default")
      (node (ref "U4") (pin "B18") (pinfunction "IO_L62P_0_B18") (pintype "bidirectional"))
    )
    (net (code "191") (name "/PLL_SPI_MISO") (class "Default")
      (node (ref "U4") (pin "A19") (pinfunction "IO_L63N_SCP6_0_A19") (pintype "bidirectional"))
    )
    (net (code "192") (name "/PLL_SPI_MOSI") (class "Default")
      (node (ref "U4") (pin "C19") (pinfunction "IO_L63P_SCP7_0_C19") (pintype "bidirectional"))
    )
    (net (code "193") (name "/PLL_SYNC") (class "Default")
      (node (ref "U4") (pin "H17") (pinfunction "IO_L59N_0_H17") (pintype "bidirectional"))
    )
    (net (code "194") (name "/PROGRAM_B") (class "Default")
      (node (ref "R66") (pin "2") (pinfunction "2_2") (pintype "passive"))
      (node (ref "R67") (pin "1") (pinfunction "1_1") (pintype "passive"))
      (node (ref "R68") (pin "1") (pinfunction "1_1") (pintype "passive"))
      (node (ref "U4") (pin "AF3") (pinfunction "PROGRAM_B_2_AF3") (pintype "bidirectional"))
    )
    (net (code "195") (name "/PROM_D0") (class "Default")
      (node (ref "U4") (pin "AD20") (pinfunction "IO_L3P_D0_DIN_MISO_MISO1_2_AD20") (pintype "bidirectional"))
    )
    (net (code "196") (name "/PROM_D1") (class "Default")
      (node (ref "U4") (pin "AE17") (pinfunction "IO_L12P_D1_MISO2_2_AE17") (pintype "bidirectional"))
    )
    (net (code "197") (name "/PROM_D2") (class "Default")
      (node (ref "U4") (pin "AF17") (pinfunction "IO_L12N_D2_MISO3_2_AF17") (pintype "bidirectional"))
    )
    (net (code "198") (name "/PROM_D3") (class "Default")
      (node (ref "U4") (pin "AD10") (pinfunction "IO_L49P_D3_2_AD10") (pintype "bidirectional"))
    )
    (net (code "199") (name "/PROM_D4") (class "Default")
      (node (ref "U4") (pin "AF10") (pinfunction "IO_L49N_D4_2_AF10") (pintype "bidirectional"))
    )
    (net (code "200") (name "/PROM_D5") (class "Default")
      (node (ref "U4") (pin "AE7") (pinfunction "IO_L62P_D5_2_AE7") (pintype "bidirectional"))
    )
    (net (code "201") (name "/PROM_D6") (class "Default")
      (node (ref "U4") (pin "AF7") (pinfunction "IO_L62N_D6_2_AF7") (pintype "bidirectional"))
    )
    (net (code "202") (name "/PROM_D7") (class "Default")
      (node (ref "U4") (pin "AE9") (pinfunction "IO_L48P_D7_2_AE9") (pintype "bidirectional"))
    )
    (net (code "204") (name "/PRSNT_PCI") (class "Default")
      (node (ref "U4") (pin "F7") (pinfunction "IO_L5N_0_F7") (pintype "bidirectional"))
    )
    (net (code "205") (name "/RAS") (class "Default")
      (node (ref "U4") (pin "K7") (pinfunction "IO_L70P_M4RASN_4_K7") (pintype "bidirectional"))
    )
    (net (code "206") (name "/REF_CLK_N") (class "Default")
      (node (ref "U4") (pin "R1") (pinfunction "IO_L44N_GCLK20_M3A6_3_R1") (pintype "bidirectional"))
    )
    (net (code "207") (name "/REF_CLK_P") (class "Default")
      (node (ref "U4") (pin "R2") (pinfunction "IO_L44P_GCLK21_M3A5_3_R2") (pintype "bidirectional"))
    )
    (net (code "208") (name "/RESET") (class "Default")
      (node (ref "U4") (pin "P10") (pinfunction "IO_L49P_M3A7_3_P10") (pintype "bidirectional"))
    )
    (net (code "209") (name "/RESET_ISO") (class "Default")
      (node (ref "U4") (pin "V10") (pinfunction "IO_L21N_3_V10") (pintype "bidirectional"))
    )
    (net (code "210") (name "/REV_SEL0") (class "Default")
      (node (ref "U4") (pin "W17") (pinfunction "IO_L8N_2_W17") (pintype "bidirectional"))
    )
    (net (code "211") (name "/REV_SEL1") (class "Default")
      (node (ref "U4") (pin "V16") (pinfunction "IO_L8P_2_V16") (pintype "bidirectional"))
    )
    (net (code "212") (name "/RFUSE") (class "Default")
      (node (ref "U4") (pin "AA20") (pinfunction "RFUSE_AA20") (pintype "input"))
    )
    (net (code "213") (name "/RST_DAC") (class "Default")
      (node (ref "U4") (pin "P7") (pinfunction "IO_L45P_M3A3_3_P7") (pintype "bidirectional"))
    )
    (net (code "214") (name "/RST_ETH_PHY") (class "Default")
      (node (ref "U4") (pin "N19") (pinfunction "IO_L36N_A8_M1BA1_1_N19") (pintype "bidirectional"))
    )
    (net (code "215") (name "/RXC") (class "Default")
      (node (ref "U4") (pin "W25") (pinfunction "IO_L44P_A3_M1DQ6_1_W25") (pintype "bidirectional"))
    )
    (net (code "216") (name "/RXD0") (class "Default")
      (node (ref "U4") (pin "V23") (pinfunction "IO_L42P_GCLK7_M1UDM_1_V23") (pintype "bidirectional"))
    )
    (net (code "217") (name "/RXD1") (class "Default")
      (node (ref "U4") (pin "W24") (pinfunction "IO_L42N_GCLK6_TRDY1_M1LDM_1_W24") (pintype "bidirectional"))
    )
    (net (code "218") (name "/RXD2") (class "Default")
      (node (ref "U4") (pin "U25") (pinfunction "IO_L43P_GCLK5_M1DQ4_1_U25") (pintype "bidirectional"))
    )
    (net (code "219") (name "/RXD3") (class "Default")
      (node (ref "U4") (pin "U26") (pinfunction "IO_L43N_GCLK4_M1DQ5_1_U26") (pintype "bidirectional"))
    )
    (net (code "220") (name "/RXDV") (class "Default")
      (node (ref "U4") (pin "P21") (pinfunction "IO_L41P_GCLK9_IRDY1_M1RASN_1_P21") (pintype "bidirectional"))
    )
    (net (code "221") (name "/RXER") (class "Default")
      (node (ref "U4") (pin "P22") (pinfunction "IO_L41N_GCLK8_M1CASN_1_P22") (pintype "bidirectional"))
    )
    (net (code "222") (name "/RZQ") (class "Default")
      (node (ref "R69") (pin "1") (pinfunction "1_1") (pintype "passive"))
      (node (ref "U4") (pin "C4") (pinfunction "IO_L83P_4_C4") (pintype "bidirectional"))
    )
    (net (code "223") (name "/SCL1") (class "Default")
      (node (ref "U4") (pin "AA11") (pinfunction "IO_L43P_2_AA11") (pintype "bidirectional"))
    )
    (net (code "224") (name "/SCL2") (class "Default")
      (node (ref "U4") (pin "R25") (pinfunction "IO_L35P_A11_M1A7_1_R25") (pintype "bidirectional"))
    )
    (net (code "225") (name "/SCL3") (class "Default")
      (node (ref "U4") (pin "AC16") (pinfunction "IO_L17P_2_AC16") (pintype "bidirectional"))
    )
    (net (code "226") (name "/SDA1") (class "Default")
      (node (ref "U4") (pin "AB11") (pinfunction "IO_L43N_2_AB11") (pintype "bidirectional"))
    )
    (net (code "227") (name "/SDA2") (class "Default")
      (node (ref "U4") (pin "R26") (pinfunction "IO_L35N_A10_M1A2_1_R26") (pintype "bidirectional"))
    )
    (net (code "228") (name "/SDA3") (class "Default")
      (node (ref "U4") (pin "AD17") (pinfunction "IO_L17N_2_AD17") (pintype "bidirectional"))
    )
    (net (code "229") (name "/SDIO") (class "Default")
      (node (ref "U4") (pin "R4") (pinfunction "IO_L46P_M3CLK_3_R4") (pintype "bidirectional"))
    )
    (net (code "230") (name "/SD_CLK") (class "Default")
      (node (ref "U4") (pin "R19") (pinfunction "IO_L57N_1_R19") (pintype "bidirectional"))
    )
    (net (code "231") (name "/SD_CMD") (class "Default")
      (node (ref "U4") (pin "R17") (pinfunction "IO_L58P_1_R17") (pintype "bidirectional"))
    )
    (net (code "232") (name "/SD_D0") (class "Default")
      (node (ref "U4") (pin "U24") (pinfunction "IO_L53N_VREF_1_U24") (pintype "bidirectional"))
    )
    (net (code "233") (name "/SD_D1") (class "Default")
      (node (ref "U4") (pin "R22") (pinfunction "IO_L55P_1_R22") (pintype "bidirectional"))
    )
    (net (code "234") (name "/SD_D2") (class "Default")
      (node (ref "U4") (pin "R21") (pinfunction "IO_L55N_1_R21") (pintype "bidirectional"))
    )
    (net (code "235") (name "/SD_D3") (class "Default")
      (node (ref "U4") (pin "P17") (pinfunction "IO_L56P_1_P17") (pintype "bidirectional"))
    )
    (net (code "236") (name "/SD_DET") (class "Default")
      (node (ref "U4") (pin "R18") (pinfunction "IO_L58N_1_R18") (pintype "bidirectional"))
    )
    (net (code "238") (name "/SEN") (class "Default")
      (node (ref "U4") (pin "R7") (pinfunction "IO_L31P_3_R7") (pintype "bidirectional"))
    )
    (net (code "239") (name "/SENSE_CS") (class "Default")
      (node (ref "U4") (pin "B6") (pinfunction "IO_L6P_0_B6") (pintype "bidirectional"))
    )
    (net (code "240") (name "/SENSE_MISO") (class "Default")
      (node (ref "U4") (pin "A7") (pinfunction "IO_L12N_0_A7") (pintype "bidirectional"))
    )
    (net (code "241") (name "/SENSE_MOSI") (class "Default")
      (node (ref "U4") (pin "A6") (pinfunction "IO_L6N_0_A6") (pintype "bidirectional"))
    )
    (net (code "242") (name "/SENSE_SCLK") (class "Default")
      (node (ref "U4") (pin "A5") (pinfunction "IO_L4N_0_A5") (pintype "bidirectional"))
    )
    (net (code "243") (name "/SERIAL_NO") (class "Default")
      (node (ref "U4") (pin "P26") (pinfunction "IO_L33N_A14_M1A4_1_P26") (pintype "bidirectional"))
    )
    (net (code "244") (name "/SLEEP_ISO") (class "Default")
      (node (ref "U4") (pin "T10") (pinfunction "IO_L25P_3_T10") (pintype "bidirectional"))
    )
    (net (code "245") (name "/SMCLK_PCI") (class "Default")
      (node (ref "U4") (pin "E10") (pinfunction "IO_L18P_0_E10") (pintype "bidirectional"))
    )
    (net (code "246") (name "/SMDAT_PCI") (class "Default")
      (node (ref "U4") (pin "F10") (pinfunction "IO_L18N_0_F10") (pintype "bidirectional"))
    )
    (net (code "247") (name "/SR_ISO") (class "Default")
      (node (ref "U4") (pin "U5") (pinfunction "IO_L24P_3_U5") (pintype "bidirectional"))
    )
    (net (code "248") (name "/STEP_ISO") (class "Default")
      (node (ref "U4") (pin "W10") (pinfunction "IO_L21P_3_W10") (pintype "bidirectional"))
    )
    (net (code "249") (name "/SUSPEND") (class "Default")
      (node (ref "U4") (pin "AD23") (pinfunction "SUSPEND_AD23") (pintype "input"))
    )
    (net (code "250") (name "/TAG_RST") (class "Default")
      (node (ref "R68") (pin "2") (pinfunction "2_2") (pintype "passive"))
    )
    (net (code "251") (name "/TCK") (class "Default")
      (node (ref "U4") (pin "E21") (pinfunction "TCK_E21") (pintype "input"))
    )
    (net (code "252") (name "/TDI") (class "Default")
      (node (ref "U4") (pin "F20") (pinfunction "TDI_F20") (pintype "input"))
    )
    (net (code "253") (name "/TDO") (class "Default")
      (node (ref "U4") (pin "A24") (pinfunction "TDO_A24") (pintype "output"))
    )
    (net (code "254") (name "/TMS") (class "Default")
      (node (ref "U4") (pin "C23") (pinfunction "TMS_C23") (pintype "input"))
    )
    (net (code "255") (name "/TXC") (class "Default")
      (node (ref "U4") (pin "W26") (pinfunction "IO_L44N_A2_M1DQ7_1_W26") (pintype "bidirectional"))
    )
    (net (code "256") (name "/TXD0") (class "Default")
      (node (ref "U4") (pin "T24") (pinfunction "IO_L46P_FCS_B_M1DQ2_1_T24") (pintype "bidirectional"))
    )
    (net (code "257") (name "/TXD1") (class "Default")
      (node (ref "U4") (pin "T26") (pinfunction "IO_L46N_FOE_B_M1DQ3_1_T26") (pintype "bidirectional"))
    )
    (net (code "258") (name "/TXD2") (class "Default")
      (node (ref "U4") (pin "Y24") (pinfunction "IO_L47P_FWE_B_M1DQ0_1_Y24") (pintype "bidirectional"))
    )
    (net (code "259") (name "/TXD3") (class "Default")
      (node (ref "U4") (pin "Y26") (pinfunction "IO_L47N_LDC_M1DQ1_1_Y26") (pintype "bidirectional"))
    )
    (net (code "260") (name "/TXEN") (class "Default")
      (node (ref "U4") (pin "V24") (pinfunction "IO_L45P_A1_M1LDQS_1_V24") (pintype "bidirectional"))
    )
    (net (code "261") (name "/TXENABLE") (class "Default")
      (node (ref "U4") (pin "N6") (pinfunction "IO_L47N_M3A1_3_N6") (pintype "bidirectional"))
    )
    (net (code "262") (name "/TXER") (class "Default")
      (node (ref "U4") (pin "V26") (pinfunction "IO_L45N_A0_M1LDQSN_1_V26") (pintype "bidirectional"))
    )
    (net (code "263") (name "/UDM") (class "Default")
      (node (ref "U4") (pin "J4") (pinfunction "IO_L69P_M4UDM_4_J4") (pintype "bidirectional"))
    )
    (net (code "264") (name "/UDQS_N") (class "Default")
      (node (ref "U4") (pin "L1") (pinfunction "IO_L61N_M4UDQSN_4_L1") (pintype "bidirectional"))
    )
    (net (code "265") (name "/UDQS_P") (class "Default")
      (node (ref "U4") (pin "L2") (pinfunction "IO_L61P_M4UDQS_4_L2") (pintype "bidirectional"))
    )
    (net (code "266") (name "/USB_CTS") (class "Default")
      (node (ref "U4") (pin "G20") (pinfunction "IO_L2P_M5A13_5_G20") (pintype "bidirectional"))
    )
    (net (code "267") (name "/USB_RTS") (class "Default")
      (node (ref "U4") (pin "G21") (pinfunction "IO_L2N_M5A14_5_G21") (pintype "bidirectional"))
    )
    (net (code "268") (name "/USB_RX") (class "Default")
      (node (ref "U4") (pin "A23") (pinfunction "IO_L1N_A24_VREF_5_A23") (pintype "bidirectional"))
    )
    (net (code "269") (name "/USB_TX") (class "Default")
      (node (ref "U4") (pin "B23") (pinfunction "IO_L1P_A25_5_B23") (pintype "bidirectional"))
    )
    (net (code "270") (name "/USM0_ISO") (class "Default")
      (node (ref "U4") (pin "U8") (pinfunction "IO_L23P_3_U8") (pintype "bidirectional"))
    )
    (net (code "271") (name "/USM1_ISO") (class "Default")
      (node (ref "U4") (pin "Y5") (pinfunction "IO_L22N_3_Y5") (pintype "bidirectional"))
    )
    (net (code "272") (name "/VBATT") (class "Default")
      (node (ref "U4") (pin "W21") (pinfunction "VBATT_W21") (pintype "power_in"))
    )
    (net (code "273") (name "/VFS") (class "Default")
      (node (ref "U4") (pin "AB19") (pinfunction "VFS_AB19") (pintype "power_in"))
    )
    (net (code "274") (name "/VTT_PG") (class "Default")
      (node (ref "U4") (pin "AA26") (pinfunction "IO_L51N_M1DQ13_1_AA26") (pintype "bidirectional"))
    )
    (net (code "275") (name "/WAKE_PCI") (class "Default")
      (node (ref "U4") (pin "C7") (pinfunction "IO_L12P_0_C7") (pintype "bidirectional"))
    )
    (net (code "276") (name "/WDTO") (class "Default")
      (node (ref "R66") (pin "1") (pinfunction "1_1") (pintype "passive"))
      (node (ref "U4") (pin "C25") (pinfunction "IO_L11P_M5CLK_5_C25") (pintype "bidirectional"))
    )
    (net (code "277") (name "/WE") (class "Default")
      (node (ref "U4") (pin "E4") (pinfunction "IO_L77P_M4WE_4_E4") (pintype "bidirectional"))
    )
    (net (code "298") (name "GND") (class "Default")
      (node (ref "C149") (pin "2") (pinfunction "2_2") (pintype "passive"))
      (node (ref "R60") (pin "2") (pinfunction "2_2") (pintype "passive"))
      (node (ref "R61") (pin "2") (pinfunction "2_2") (pintype "passive"))
      (node (ref "R64") (pin "2") (pinfunction "2_2") (pintype "passive"))
      (node (ref "R69") (pin "2") (pinfunction "2_2") (pintype "passive"))
    )
    (net (code "299") (name "unconnected-(U4A-IO_L1N_VREF_0-PadA2)") (class "Default")
      (node (ref "U4") (pin "A2") (pinfunction "IO_L1N_VREF_0_A2") (pintype "bidirectional"))
    )
    (net (code "300") (name "unconnected-(U4A-IO_L1P_HSWAPEN_0-PadA3)") (class "Default")
      (node (ref "U4") (pin "A3") (pinfunction "IO_L1P_HSWAPEN_0_A3") (pintype "bidirectional"))
    )
    (net (code "301") (name "unconnected-(U4A-IO_L2N_0-PadA4)") (class "Default")
      (node (ref "U4") (pin "A4") (pinfunction "IO_L2N_0_A4") (pintype "bidirectional"))
    )
    (net (code "302") (name "unconnected-(U4A-IO_L2P_0-PadB4)") (class "Default")
      (node (ref "U4") (pin "B4") (pinfunction "IO_L2P_0_B4") (pintype "bidirectional"))
    )
    (net (code "303") (name "unconnected-(U4A-IO_L3N_0-PadD5)") (class "Default")
      (node (ref "U4") (pin "D5") (pinfunction "IO_L3N_0_D5") (pintype "bidirectional"))
    )
    (net (code "304") (name "unconnected-(U4A-IO_L3P_0-PadE6)") (class "Default")
      (node (ref "U4") (pin "E6") (pinfunction "IO_L3P_0_E6") (pintype "bidirectional"))
    )
    (net (code "305") (name "unconnected-(U4A-IO_L4P_0-PadC5)") (class "Default")
      (node (ref "U4") (pin "C5") (pinfunction "IO_L4P_0_C5") (pintype "bidirectional"))
    )
    (net (code "306") (name "unconnected-(U4A-IO_L26N_0-PadA12)") (class "Default")
      (node (ref "U4") (pin "A12") (pinfunction "IO_L26N_0_A12") (pintype "bidirectional"))
    )
    (net (code "307") (name "unconnected-(U4A-IO_L26P_0-PadB12)") (class "Default")
      (node (ref "U4") (pin "B12") (pinfunction "IO_L26P_0_B12") (pintype "bidirectional"))
    )
    (net (code "308") (name "unconnected-(U4A-IO_L31N_0-PadC12)") (class "Default")
      (node (ref "U4") (pin "C12") (pinfunction "IO_L31N_0_C12") (pintype "bidirectional"))
    )
    (net (code "309") (name "unconnected-(U4A-IO_L31P_0-PadD12)") (class "Default")
      (node (ref "U4") (pin "D12") (pinfunction "IO_L31P_0_D12") (pintype "bidirectional"))
    )
    (net (code "310") (name "unconnected-(U4A-IO_L33N_0-PadD13)") (class "Default")
      (node (ref "U4") (pin "D13") (pinfunction "IO_L33N_0_D13") (pintype "bidirectional"))
    )
    (net (code "311") (name "unconnected-(U4A-IO_L33P_0-PadF13)") (class "Default")
      (node (ref "U4") (pin "F13") (pinfunction "IO_L33P_0_F13") (pintype "bidirectional"))
    )
    (net (code "312") (name "unconnected-(U4A-IO_L44N_0-PadD15)") (class "Default")
      (node (ref "U4") (pin "D15") (pinfunction "IO_L44N_0_D15") (pintype "bidirectional"))
    )
    (net (code "313") (name "unconnected-(U4A-IO_L44P_0-PadE14)") (class "Default")
      (node (ref "U4") (pin "E14") (pinfunction "IO_L44P_0_E14") (pintype "bidirectional"))
    )
    (net (code "314") (name "unconnected-(U4A-IO_L55N_0-PadG17)") (class "Default")
      (node (ref "U4") (pin "G17") (pinfunction "IO_L55N_0_G17") (pintype "bidirectional"))
    )
    (net (code "315") (name "unconnected-(U4A-IO_L55P_0-PadH16)") (class "Default")
      (node (ref "U4") (pin "H16") (pinfunction "IO_L55P_0_H16") (pintype "bidirectional"))
    )
    (net (code "316") (name "unconnected-(U4A-IO_L57N_0-PadE18)") (class "Default")
      (node (ref "U4") (pin "E18") (pinfunction "IO_L57N_0_E18") (pintype "bidirectional"))
    )
    (net (code "317") (name "unconnected-(U4A-IO_L57P_0-PadF18)") (class "Default")
      (node (ref "U4") (pin "F18") (pinfunction "IO_L57P_0_F18") (pintype "bidirectional"))
    )
    (net (code "318") (name "unconnected-(U4A-IO_L59P_0-PadJ17)") (class "Default")
      (node (ref "U4") (pin "J17") (pinfunction "IO_L59P_0_J17") (pintype "bidirectional"))
    )
    (net (code "319") (name "unconnected-(U4A-IO_L66N_SCP0_0-PadA22)") (class "Default")
      (node (ref "U4") (pin "A22") (pinfunction "IO_L66N_SCP0_0_A22") (pintype "bidirectional"))
    )
    (net (code "320") (name "unconnected-(U4B-IO_L28N_VREF_1-PadK19)") (class "Default")
      (node (ref "U4") (pin "K19") (pinfunction "IO_L28N_VREF_1_K19") (pintype "bidirectional"))
    )
    (net (code "321") (name "unconnected-(U4B-IO_L28P_1-PadL19)") (class "Default")
      (node (ref "U4") (pin "L19") (pinfunction "IO_L28P_1_L19") (pintype "bidirectional"))
    )
    (net (code "322") (name "unconnected-(U4B-IO_L29N_A22_M1A14_1-PadL24)") (class "Default")
      (node (ref "U4") (pin "L24") (pinfunction "IO_L29N_A22_M1A14_1_L24") (pintype "bidirectional"))
    )
    (net (code "323") (name "unconnected-(U4B-IO_L29P_A23_M1A13_1-PadL23)") (class "Default")
      (node (ref "U4") (pin "L23") (pinfunction "IO_L29P_A23_M1A13_1_L23") (pintype "bidirectional"))
    )
    (net (code "324") (name "unconnected-(U4B-IO_L30N_A20_M1A11_1-PadN21)") (class "Default")
      (node (ref "U4") (pin "N21") (pinfunction "IO_L30N_A20_M1A11_1_N21") (pintype "bidirectional"))
    )
    (net (code "325") (name "unconnected-(U4B-IO_L30P_A21_M1RESET_1-PadP20)") (class "Default")
      (node (ref "U4") (pin "P20") (pinfunction "IO_L30P_A21_M1RESET_1_P20") (pintype "bidirectional"))
    )
    (net (code "326") (name "unconnected-(U4B-IO_L31N_A18_M1A12_1-PadN24)") (class "Default")
      (node (ref "U4") (pin "N24") (pinfunction "IO_L31N_A18_M1A12_1_N24") (pintype "bidirectional"))
    )
    (net (code "327") (name "unconnected-(U4B-IO_L31P_A19_M1CKE_1-PadM23)") (class "Default")
      (node (ref "U4") (pin "M23") (pinfunction "IO_L31P_A19_M1CKE_1_M23") (pintype "bidirectional"))
    )
    (net (code "328") (name "unconnected-(U4B-IO_L32N_A16_M1A9_1-PadK18)") (class "Default")
      (node (ref "U4") (pin "K18") (pinfunction "IO_L32N_A16_M1A9_1_K18") (pintype "bidirectional"))
    )
    (net (code "329") (name "unconnected-(U4B-IO_L32P_A17_M1A8_1-PadL17)") (class "Default")
      (node (ref "U4") (pin "L17") (pinfunction "IO_L32P_A17_M1A8_1_L17") (pintype "bidirectional"))
    )
    (net (code "330") (name "unconnected-(U4B-IO_L33P_A15_M1A10_1-PadP24)") (class "Default")
      (node (ref "U4") (pin "P24") (pinfunction "IO_L33P_A15_M1A10_1_P24") (pintype "bidirectional"))
    )
    (net (code "331") (name "unconnected-(U4B-IO_L34N_A12_M1BA2_1-PadL18)") (class "Default")
      (node (ref "U4") (pin "L18") (pinfunction "IO_L34N_A12_M1BA2_1_L18") (pintype "bidirectional"))
    )
    (net (code "332") (name "unconnected-(U4B-IO_L34P_A13_M1WE_1-PadM19)") (class "Default")
      (node (ref "U4") (pin "M19") (pinfunction "IO_L34P_A13_M1WE_1_M19") (pintype "bidirectional"))
    )
    (net (code "333") (name "unconnected-(U4B-IO_L36P_A9_M1BA0_1-PadM18)") (class "Default")
      (node (ref "U4") (pin "M18") (pinfunction "IO_L36P_A9_M1BA0_1_M18") (pintype "bidirectional"))
    )
    (net (code "334") (name "unconnected-(U4B-IO_L37N_A6_M1A1_1-PadN23)") (class "Default")
      (node (ref "U4") (pin "N23") (pinfunction "IO_L37N_A6_M1A1_1_N23") (pintype "bidirectional"))
    )
    (net (code "335") (name "unconnected-(U4B-IO_L37P_A7_M1A0_1-PadN22)") (class "Default")
      (node (ref "U4") (pin "N22") (pinfunction "IO_L37P_A7_M1A0_1_N22") (pintype "bidirectional"))
    )
    (net (code "336") (name "unconnected-(U4B-IO_L38N_A4_M1CLKN_1-PadN18)") (class "Default")
      (node (ref "U4") (pin "N18") (pinfunction "IO_L38N_A4_M1CLKN_1_N18") (pintype "bidirectional"))
    )
    (net (code "337") (name "unconnected-(U4B-IO_L38P_A5_M1CLK_1-PadN17)") (class "Default")
      (node (ref "U4") (pin "N17") (pinfunction "IO_L38P_A5_M1CLK_1_N17") (pintype "bidirectional"))
    )
    (net (code "338") (name "unconnected-(U4B-IO_L48N_M1DQ9_1-PadAD26)") (class "Default")
      (node (ref "U4") (pin "AD26") (pinfunction "IO_L48N_M1DQ9_1_AD26") (pintype "bidirectional"))
    )
    (net (code "339") (name "unconnected-(U4B-IO_L48P_HDC_M1DQ8_1-PadAD24)") (class "Default")
      (node (ref "U4") (pin "AD24") (pinfunction "IO_L48P_HDC_M1DQ8_1_AD24") (pintype "bidirectional"))
    )
    (net (code "340") (name "unconnected-(U4B-IO_L49N_M1DQ11_1-PadAB26)") (class "Default")
      (node (ref "U4") (pin "AB26") (pinfunction "IO_L49N_M1DQ11_1_AB26") (pintype "bidirectional"))
    )
    (net (code "341") (name "unconnected-(U4B-IO_L50N_M1UDQSN_1-PadAC26)") (class "Default")
      (node (ref "U4") (pin "AC26") (pinfunction "IO_L50N_M1UDQSN_1_AC26") (pintype "bidirectional"))
    )
    (net (code "342") (name "unconnected-(U4B-IO_L50P_M1UDQS_1-PadAC25)") (class "Default")
      (node (ref "U4") (pin "AC25") (pinfunction "IO_L50P_M1UDQS_1_AC25") (pintype "bidirectional"))
    )
    (net (code "343") (name "unconnected-(U4B-IO_L53P_1-PadT23)") (class "Default")
      (node (ref "U4") (pin "T23") (pinfunction "IO_L53P_1_T23") (pintype "bidirectional"))
    )
    (net (code "344") (name "unconnected-(U4B-IO_L59N_1-PadU23)") (class "Default")
      (node (ref "U4") (pin "U23") (pinfunction "IO_L59N_1_U23") (pintype "bidirectional"))
    )
    (net (code "345") (name "unconnected-(U4B-IO_L59P_1-PadT22)") (class "Default")
      (node (ref "U4") (pin "T22") (pinfunction "IO_L59P_1_T22") (pintype "bidirectional"))
    )
    (net (code "346") (name "unconnected-(U4B-IO_L60N_1-PadT19)") (class "Default")
      (node (ref "U4") (pin "T19") (pinfunction "IO_L60N_1_T19") (pintype "bidirectional"))
    )
    (net (code "347") (name "unconnected-(U4B-IO_L60P_1-PadT18)") (class "Default")
      (node (ref "U4") (pin "T18") (pinfunction "IO_L60P_1_T18") (pintype "bidirectional"))
    )
    (net (code "348") (name "unconnected-(U4B-IO_L61N_1-PadU22)") (class "Default")
      (node (ref "U4") (pin "U22") (pinfunction "IO_L61N_1_U22") (pintype "bidirectional"))
    )
    (net (code "349") (name "unconnected-(U4B-IO_L61P_1-PadU21)") (class "Default")
      (node (ref "U4") (pin "U21") (pinfunction "IO_L61P_1_U21") (pintype "bidirectional"))
    )
    (net (code "350") (name "unconnected-(U4B-IO_L62N_1-PadV17)") (class "Default")
      (node (ref "U4") (pin "V17") (pinfunction "IO_L62N_1_V17") (pintype "bidirectional"))
    )
    (net (code "351") (name "unconnected-(U4B-IO_L62P_1-PadU17)") (class "Default")
      (node (ref "U4") (pin "U17") (pinfunction "IO_L62P_1_U17") (pintype "bidirectional"))
    )
    (net (code "352") (name "unconnected-(U4B-IO_L63N_1-PadAA24)") (class "Default")
      (node (ref "U4") (pin "AA24") (pinfunction "IO_L63N_1_AA24") (pintype "bidirectional"))
    )
    (net (code "353") (name "unconnected-(U4B-IO_L63P_1-PadAA23)") (class "Default")
      (node (ref "U4") (pin "AA23") (pinfunction "IO_L63P_1_AA23") (pintype "bidirectional"))
    )
    (net (code "354") (name "unconnected-(U4B-IO_L64N_1-PadU20)") (class "Default")
      (node (ref "U4") (pin "U20") (pinfunction "IO_L64N_1_U20") (pintype "bidirectional"))
    )
    (net (code "355") (name "unconnected-(U4B-IO_L65N_1-PadAC24)") (class "Default")
      (node (ref "U4") (pin "AC24") (pinfunction "IO_L65N_1_AC24") (pintype "bidirectional"))
    )
    (net (code "356") (name "unconnected-(U4B-IO_L65P_1-PadAC23)") (class "Default")
      (node (ref "U4") (pin "AC23") (pinfunction "IO_L65P_1_AC23") (pintype "bidirectional"))
    )
    (net (code "357") (name "unconnected-(U4B-IO_L66N_1-PadV19)") (class "Default")
      (node (ref "U4") (pin "V19") (pinfunction "IO_L66N_1_V19") (pintype "bidirectional"))
    )
    (net (code "358") (name "unconnected-(U4B-IO_L66P_1-PadV18)") (class "Default")
      (node (ref "U4") (pin "V18") (pinfunction "IO_L66P_1_V18") (pintype "bidirectional"))
    )
    (net (code "359") (name "unconnected-(U4B-IO_L67N_1-PadAF25)") (class "Default")
      (node (ref "U4") (pin "AF25") (pinfunction "IO_L67N_1_AF25") (pintype "bidirectional"))
    )
    (net (code "360") (name "unconnected-(U4B-IO_L67P_1-PadAE24)") (class "Default")
      (node (ref "U4") (pin "AE24") (pinfunction "IO_L67P_1_AE24") (pintype "bidirectional"))
    )
    (net (code "361") (name "unconnected-(U4B-IO_L68N_1-PadW19)") (class "Default")
      (node (ref "U4") (pin "W19") (pinfunction "IO_L68N_1_W19") (pintype "bidirectional"))
    )
    (net (code "362") (name "unconnected-(U4B-IO_L68P_1-PadW18)") (class "Default")
      (node (ref "U4") (pin "W18") (pinfunction "IO_L68P_1_W18") (pintype "bidirectional"))
    )
    (net (code "363") (name "unconnected-(U4B-IO_L69N_VREF_1-PadAB22)") (class "Default")
      (node (ref "U4") (pin "AB22") (pinfunction "IO_L69N_VREF_1_AB22") (pintype "bidirectional"))
    )
    (net (code "364") (name "unconnected-(U4B-IO_L69P_1-PadAB21)") (class "Default")
      (node (ref "U4") (pin "AB21") (pinfunction "IO_L69P_1_AB21") (pintype "bidirectional"))
    )
    (net (code "365") (name "unconnected-(U4B-IO_L70N_1-PadV20)") (class "Default")
      (node (ref "U4") (pin "V20") (pinfunction "IO_L70N_1_V20") (pintype "bidirectional"))
    )
    (net (code "366") (name "unconnected-(U4B-IO_L70P_1-PadU19)") (class "Default")
      (node (ref "U4") (pin "U19") (pinfunction "IO_L70P_1_U19") (pintype "bidirectional"))
    )
    (net (code "367") (name "unconnected-(U4B-IO_L71N_1-PadW22)") (class "Default")
      (node (ref "U4") (pin "W22") (pinfunction "IO_L71N_1_W22") (pintype "bidirectional"))
    )
    (net (code "368") (name "unconnected-(U4B-IO_L71P_1-PadV22)") (class "Default")
      (node (ref "U4") (pin "V22") (pinfunction "IO_L71P_1_V22") (pintype "bidirectional"))
    )
    (net (code "369") (name "unconnected-(U4B-IO_L72N_1-PadY21)") (class "Default")
      (node (ref "U4") (pin "Y21") (pinfunction "IO_L72N_1_Y21") (pintype "bidirectional"))
    )
    (net (code "370") (name "unconnected-(U4B-IO_L72P_1-PadY20)") (class "Default")
      (node (ref "U4") (pin "Y20") (pinfunction "IO_L72P_1_Y20") (pintype "bidirectional"))
    )
    (net (code "371") (name "unconnected-(U4B-IO_L73N_1-PadAA22)") (class "Default")
      (node (ref "U4") (pin "AA22") (pinfunction "IO_L73N_1_AA22") (pintype "bidirectional"))
    )
    (net (code "372") (name "unconnected-(U4B-IO_L73P_1-PadY22)") (class "Default")
      (node (ref "U4") (pin "Y22") (pinfunction "IO_L73P_1_Y22") (pintype "bidirectional"))
    )
    (net (code "373") (name "unconnected-(U4B-IO_L74N_DOUT_BUSY_1-PadAF24)") (class "Default")
      (node (ref "U4") (pin "AF24") (pinfunction "IO_L74N_DOUT_BUSY_1_AF24") (pintype "bidirectional"))
    )
    (net (code "374") (name "unconnected-(U4B-IO_L74P_AWAKE_1-PadAE23)") (class "Default")
      (node (ref "U4") (pin "AE23") (pinfunction "IO_L74P_AWAKE_1_AE23") (pintype "bidirectional"))
    )
    (net (code "375") (name "unconnected-(U4C-CMPCS_B_2-PadAC22)") (class "Default")
      (node (ref "U4") (pin "AC22") (pinfunction "CMPCS_B_2_AC22") (pintype "bidirectional"))
    )
    (net (code "376") (name "unconnected-(U4C-IO_L2N_CMPMOSI_2-PadAF21)") (class "Default")
      (node (ref "U4") (pin "AF21") (pinfunction "IO_L2N_CMPMOSI_2_AF21") (pintype "bidirectional"))
    )
    (net (code "377") (name "unconnected-(U4C-IO_L2P_CMPCLK_2-PadAE21)") (class "Default")
      (node (ref "U4") (pin "AE21") (pinfunction "IO_L2P_CMPCLK_2_AE21") (pintype "bidirectional"))
    )
    (net (code "378") (name "unconnected-(U4C-IO_L3N_MOSI_CSI_B_MISO0_2-PadAF20)") (class "Default")
      (node (ref "U4") (pin "AF20") (pinfunction "IO_L3N_MOSI_CSI_B_MISO0_2_AF20") (pintype "bidirectional"))
    )
    (net (code "379") (name "unconnected-(U4C-IO_L4N_VREF_2-PadAF19)") (class "Default")
      (node (ref "U4") (pin "AF19") (pinfunction "IO_L4N_VREF_2_AF19") (pintype "bidirectional"))
    )
    (net (code "380") (name "unconnected-(U4C-IO_L4P_2-PadAE19)") (class "Default")
      (node (ref "U4") (pin "AE19") (pinfunction "IO_L4P_2_AE19") (pintype "bidirectional"))
    )
    (net (code "381") (name "unconnected-(U4C-IO_L5N_2-PadAD21)") (class "Default")
      (node (ref "U4") (pin "AD21") (pinfunction "IO_L5N_2_AD21") (pintype "bidirectional"))
    )
    (net (code "382") (name "unconnected-(U4C-IO_L5P_2-PadAC20)") (class "Default")
      (node (ref "U4") (pin "AC20") (pinfunction "IO_L5P_2_AC20") (pintype "bidirectional"))
    )
    (net (code "383") (name "unconnected-(U4C-IO_L6N_2-PadAA19)") (class "Default")
      (node (ref "U4") (pin "AA19") (pinfunction "IO_L6N_2_AA19") (pintype "bidirectional"))
    )
    (net (code "384") (name "unconnected-(U4C-IO_L6P_2-PadY18)") (class "Default")
      (node (ref "U4") (pin "Y18") (pinfunction "IO_L6P_2_Y18") (pintype "bidirectional"))
    )
    (net (code "385") (name "unconnected-(U4C-IO_L7P_2-PadAC19)") (class "Default")
      (node (ref "U4") (pin "AC19") (pinfunction "IO_L7P_2_AC19") (pintype "bidirectional"))
    )
    (net (code "386") (name "unconnected-(U4C-IO_L11N_2-PadAB18)") (class "Default")
      (node (ref "U4") (pin "AB18") (pinfunction "IO_L11N_2_AB18") (pintype "bidirectional"))
    )
    (net (code "387") (name "unconnected-(U4C-IO_L11P_2-PadAA18)") (class "Default")
      (node (ref "U4") (pin "AA18") (pinfunction "IO_L11P_2_AA18") (pintype "bidirectional"))
    )
    (net (code "388") (name "unconnected-(U4C-IO_L13N_D10_2-PadAF16)") (class "Default")
      (node (ref "U4") (pin "AF16") (pinfunction "IO_L13N_D10_2_AF16") (pintype "bidirectional"))
    )
    (net (code "389") (name "unconnected-(U4C-IO_L14N_D12_2-PadAF15)") (class "Default")
      (node (ref "U4") (pin "AF15") (pinfunction "IO_L14N_D12_2_AF15") (pintype "bidirectional"))
    )
    (net (code "390") (name "unconnected-(U4C-IO_L14P_D11_2-PadAE15)") (class "Default")
      (node (ref "U4") (pin "AE15") (pinfunction "IO_L14P_D11_2_AE15") (pintype "bidirectional"))
    )
    (net (code "391") (name "unconnected-(U4C-IO_L15N_2-PadAC17)") (class "Default")
      (node (ref "U4") (pin "AC17") (pinfunction "IO_L15N_2_AC17") (pintype "bidirectional"))
    )
    (net (code "392") (name "unconnected-(U4C-IO_L15P_2-PadAB17)") (class "Default")
      (node (ref "U4") (pin "AB17") (pinfunction "IO_L15P_2_AB17") (pintype "bidirectional"))
    )
    (net (code "393") (name "unconnected-(U4C-IO_L16N_VREF_2-PadAD15)") (class "Default")
      (node (ref "U4") (pin "AD15") (pinfunction "IO_L16N_VREF_2_AD15") (pintype "bidirectional"))
    )
    (net (code "394") (name "unconnected-(U4C-IO_L16P_2-PadAC15)") (class "Default")
      (node (ref "U4") (pin "AC15") (pinfunction "IO_L16P_2_AC15") (pintype "bidirectional"))
    )
    (net (code "395") (name "unconnected-(U4C-IO_L18N_2-PadW16)") (class "Default")
      (node (ref "U4") (pin "W16") (pinfunction "IO_L18N_2_W16") (pintype "bidirectional"))
    )
    (net (code "396") (name "unconnected-(U4C-IO_L18P_2-PadV15)") (class "Default")
      (node (ref "U4") (pin "V15") (pinfunction "IO_L18P_2_V15") (pintype "bidirectional"))
    )
    (net (code "397") (name "unconnected-(U4C-IO_L19N_2-PadAC14)") (class "Default")
      (node (ref "U4") (pin "AC14") (pinfunction "IO_L19N_2_AC14") (pintype "bidirectional"))
    )
    (net (code "398") (name "unconnected-(U4C-IO_L19P_2-PadAB15)") (class "Default")
      (node (ref "U4") (pin "AB15") (pinfunction "IO_L19P_2_AB15") (pintype "bidirectional"))
    )
    (net (code "399") (name "unconnected-(U4C-IO_L20N_2-PadAA15)") (class "Default")
      (node (ref "U4") (pin "AA15") (pinfunction "IO_L20N_2_AA15") (pintype "bidirectional"))
    )
    (net (code "400") (name "unconnected-(U4C-IO_L28N_2-PadAA14)") (class "Default")
      (node (ref "U4") (pin "AA14") (pinfunction "IO_L28N_2_AA14") (pintype "bidirectional"))
    )
    (net (code "401") (name "unconnected-(U4C-IO_L29N_GCLK2_2-PadAF14)") (class "Default")
      (node (ref "U4") (pin "AF14") (pinfunction "IO_L29N_GCLK2_2_AF14") (pintype "bidirectional"))
    )
    (net (code "402") (name "unconnected-(U4C-IO_L29P_GCLK3_2-PadAD14)") (class "Default")
      (node (ref "U4") (pin "AD14") (pinfunction "IO_L29P_GCLK3_2_AD14") (pintype "bidirectional"))
    )
    (net (code "403") (name "unconnected-(U4C-IO_L30N_GCLK0_USERCCLK_2-PadAF13)") (class "Default")
      (node (ref "U4") (pin "AF13") (pinfunction "IO_L30N_GCLK0_USERCCLK_2_AF13") (pintype "bidirectional"))
    )
    (net (code "404") (name "unconnected-(U4C-IO_L30P_GCLK1_D13_2-PadAE13)") (class "Default")
      (node (ref "U4") (pin "AE13") (pinfunction "IO_L30P_GCLK1_D13_2_AE13") (pintype "bidirectional"))
    )
    (net (code "405") (name "unconnected-(U4C-IO_L42N_2-PadV14)") (class "Default")
      (node (ref "U4") (pin "V14") (pinfunction "IO_L42N_2_V14") (pintype "bidirectional"))
    )
    (net (code "406") (name "unconnected-(U4C-IO_L42P_2-PadU15)") (class "Default")
      (node (ref "U4") (pin "U15") (pinfunction "IO_L42P_2_U15") (pintype "bidirectional"))
    )
    (net (code "407") (name "unconnected-(U4C-IO_L44N_2-PadW14)") (class "Default")
      (node (ref "U4") (pin "W14") (pinfunction "IO_L44N_2_W14") (pintype "bidirectional"))
    )
    (net (code "408") (name "unconnected-(U4C-IO_L44P_2-PadV13)") (class "Default")
      (node (ref "U4") (pin "V13") (pinfunction "IO_L44P_2_V13") (pintype "bidirectional"))
    )
    (net (code "409") (name "unconnected-(U4C-IO_L45P_2-PadAC11)") (class "Default")
      (node (ref "U4") (pin "AC11") (pinfunction "IO_L45P_2_AC11") (pintype "bidirectional"))
    )
    (net (code "410") (name "unconnected-(U4C-IO_L46N_2-PadW12)") (class "Default")
      (node (ref "U4") (pin "W12") (pinfunction "IO_L46N_2_W12") (pintype "bidirectional"))
    )
    (net (code "411") (name "unconnected-(U4C-IO_L46P_2-PadV12)") (class "Default")
      (node (ref "U4") (pin "V12") (pinfunction "IO_L46P_2_V12") (pintype "bidirectional"))
    )
    (net (code "412") (name "unconnected-(U4C-IO_L50N_2-PadU12)") (class "Default")
      (node (ref "U4") (pin "U12") (pinfunction "IO_L50N_2_U12") (pintype "bidirectional"))
    )
    (net (code "413") (name "unconnected-(U4C-IO_L50P_2-PadU13)") (class "Default")
      (node (ref "U4") (pin "U13") (pinfunction "IO_L50P_2_U13") (pintype "bidirectional"))
    )
    (net (code "414") (name "unconnected-(U4C-IO_L51N_2-PadAB10)") (class "Default")
      (node (ref "U4") (pin "AB10") (pinfunction "IO_L51N_2_AB10") (pintype "bidirectional"))
    )
    (net (code "415") (name "unconnected-(U4C-IO_L51P_2-PadY10)") (class "Default")
      (node (ref "U4") (pin "Y10") (pinfunction "IO_L51P_2_Y10") (pintype "bidirectional"))
    )
    (net (code "416") (name "unconnected-(U4C-IO_L52N_2-PadW11)") (class "Default")
      (node (ref "U4") (pin "W11") (pinfunction "IO_L52N_2_W11") (pintype "bidirectional"))
    )
    (net (code "417") (name "unconnected-(U4C-IO_L52P_2-PadV11)") (class "Default")
      (node (ref "U4") (pin "V11") (pinfunction "IO_L52P_2_V11") (pintype "bidirectional"))
    )
    (net (code "418") (name "unconnected-(U4C-IO_L53N_2-PadAF8)") (class "Default")
      (node (ref "U4") (pin "AF8") (pinfunction "IO_L53N_2_AF8") (pintype "bidirectional"))
    )
    (net (code "419") (name "unconnected-(U4C-IO_L53P_2-PadAD8)") (class "Default")
      (node (ref "U4") (pin "AD8") (pinfunction "IO_L53P_2_AD8") (pintype "bidirectional"))
    )
    (net (code "420") (name "unconnected-(U4C-IO_L58N_2-PadAD9)") (class "Default")
      (node (ref "U4") (pin "AD9") (pinfunction "IO_L58N_2_AD9") (pintype "bidirectional"))
    )
    (net (code "421") (name "unconnected-(U4C-IO_L58P_2-PadAC9)") (class "Default")
      (node (ref "U4") (pin "AC9") (pinfunction "IO_L58P_2_AC9") (pintype "bidirectional"))
    )
    (net (code "422") (name "unconnected-(U4C-IO_L61N_VREF_2-PadAB9)") (class "Default")
      (node (ref "U4") (pin "AB9") (pinfunction "IO_L61N_VREF_2_AB9") (pintype "bidirectional"))
    )
    (net (code "423") (name "unconnected-(U4C-IO_L61P_2-PadAA9)") (class "Default")
      (node (ref "U4") (pin "AA9") (pinfunction "IO_L61P_2_AA9") (pintype "bidirectional"))
    )
    (net (code "424") (name "unconnected-(U4C-IO_L63N_2-PadAF6)") (class "Default")
      (node (ref "U4") (pin "AF6") (pinfunction "IO_L63N_2_AF6") (pintype "bidirectional"))
    )
    (net (code "425") (name "unconnected-(U4C-IO_L63P_2-PadAD6)") (class "Default")
      (node (ref "U4") (pin "AD6") (pinfunction "IO_L63P_2_AD6") (pintype "bidirectional"))
    )
    (net (code "426") (name "unconnected-(U4C-IO_L64N_D9_2-PadAF5)") (class "Default")
      (node (ref "U4") (pin "AF5") (pinfunction "IO_L64N_D9_2_AF5") (pintype "bidirectional"))
    )
    (net (code "427") (name "unconnected-(U4C-IO_L64P_D8_2-PadAE5)") (class "Default")
      (node (ref "U4") (pin "AE5") (pinfunction "IO_L64P_D8_2_AE5") (pintype "bidirectional"))
    )
    (net (code "428") (name "unconnected-(U4C-IO_L65N_CSO_B_2-PadAF4)") (class "Default")
      (node (ref "U4") (pin "AF4") (pinfunction "IO_L65N_CSO_B_2_AF4") (pintype "bidirectional"))
    )
    (net (code "429") (name "unconnected-(U4D-IO_L1N_VREF_3-PadAD7)") (class "Default")
      (node (ref "U4") (pin "AD7") (pinfunction "IO_L1N_VREF_3_AD7") (pintype "bidirectional"))
    )
    (net (code "430") (name "unconnected-(U4D-IO_L1P_3-PadAC7)") (class "Default")
      (node (ref "U4") (pin "AC7") (pinfunction "IO_L1P_3_AC7") (pintype "bidirectional"))
    )
    (net (code "431") (name "unconnected-(U4D-IO_L2N_3-PadAF2)") (class "Default")
      (node (ref "U4") (pin "AF2") (pinfunction "IO_L2N_3_AF2") (pintype "bidirectional"))
    )
    (net (code "432") (name "unconnected-(U4D-IO_L2P_3-PadAE3)") (class "Default")
      (node (ref "U4") (pin "AE3") (pinfunction "IO_L2P_3_AE3") (pintype "bidirectional"))
    )
    (net (code "433") (name "unconnected-(U4D-IO_L3N_3-PadAD4)") (class "Default")
      (node (ref "U4") (pin "AD4") (pinfunction "IO_L3N_3_AD4") (pintype "bidirectional"))
    )
    (net (code "434") (name "unconnected-(U4D-IO_L3P_3-PadAC4)") (class "Default")
      (node (ref "U4") (pin "AC4") (pinfunction "IO_L3P_3_AC4") (pintype "bidirectional"))
    )
    (net (code "435") (name "unconnected-(U4D-IO_L4N_3-PadAB8)") (class "Default")
      (node (ref "U4") (pin "AB8") (pinfunction "IO_L4N_3_AB8") (pintype "bidirectional"))
    )
    (net (code "436") (name "unconnected-(U4D-IO_L4P_3-PadAA8)") (class "Default")
      (node (ref "U4") (pin "AA8") (pinfunction "IO_L4P_3_AA8") (pintype "bidirectional"))
    )
    (net (code "437") (name "unconnected-(U4D-IO_L7N_3-PadY6)") (class "Default")
      (node (ref "U4") (pin "Y6") (pinfunction "IO_L7N_3_Y6") (pintype "bidirectional"))
    )
    (net (code "438") (name "unconnected-(U4D-IO_L7P_3-PadAA7)") (class "Default")
      (node (ref "U4") (pin "AA7") (pinfunction "IO_L7P_3_AA7") (pintype "bidirectional"))
    )
    (net (code "439") (name "unconnected-(U4D-IO_L8N_3-PadAB6)") (class "Default")
      (node (ref "U4") (pin "AB6") (pinfunction "IO_L8N_3_AB6") (pintype "bidirectional"))
    )
    (net (code "440") (name "unconnected-(U4D-IO_L8P_3-PadAB7)") (class "Default")
      (node (ref "U4") (pin "AB7") (pinfunction "IO_L8P_3_AB7") (pintype "bidirectional"))
    )
    (net (code "441") (name "unconnected-(U4D-IO_L9N_3-PadY8)") (class "Default")
      (node (ref "U4") (pin "Y8") (pinfunction "IO_L9N_3_Y8") (pintype "bidirectional"))
    )
    (net (code "442") (name "unconnected-(U4D-IO_L9P_3-PadY9)") (class "Default")
      (node (ref "U4") (pin "Y9") (pinfunction "IO_L9P_3_Y9") (pintype "bidirectional"))
    )
    (net (code "443") (name "unconnected-(U4D-IO_L10N_3-PadAD5)") (class "Default")
      (node (ref "U4") (pin "AD5") (pinfunction "IO_L10N_3_AD5") (pintype "bidirectional"))
    )
    (net (code "444") (name "unconnected-(U4D-IO_L10P_3-PadAC5)") (class "Default")
      (node (ref "U4") (pin "AC5") (pinfunction "IO_L10P_3_AC5") (pintype "bidirectional"))
    )
    (net (code "445") (name "unconnected-(U4D-IO_L15N_3-PadW7)") (class "Default")
      (node (ref "U4") (pin "W7") (pinfunction "IO_L15N_3_W7") (pintype "bidirectional"))
    )
    (net (code "446") (name "unconnected-(U4D-IO_L15P_3-PadW8)") (class "Default")
      (node (ref "U4") (pin "W8") (pinfunction "IO_L15P_3_W8") (pintype "bidirectional"))
    )
    (net (code "447") (name "unconnected-(U4D-IO_L16N_3-PadAB5)") (class "Default")
      (node (ref "U4") (pin "AB5") (pinfunction "IO_L16N_3_AB5") (pintype "bidirectional"))
    )
    (net (code "448") (name "unconnected-(U4D-IO_L16P_3-PadAA5)") (class "Default")
      (node (ref "U4") (pin "AA5") (pinfunction "IO_L16P_3_AA5") (pintype "bidirectional"))
    )
    (net (code "449") (name "unconnected-(U4D-IO_L17N_VREF_3-PadV6)") (class "Default")
      (node (ref "U4") (pin "V6") (pinfunction "IO_L17N_VREF_3_V6") (pintype "bidirectional"))
    )
    (net (code "450") (name "unconnected-(U4D-IO_L17P_3-PadV7)") (class "Default")
      (node (ref "U4") (pin "V7") (pinfunction "IO_L17P_3_V7") (pintype "bidirectional"))
    )
    (net (code "451") (name "unconnected-(U4D-IO_L18N_3-PadAC3)") (class "Default")
      (node (ref "U4") (pin "AC3") (pinfunction "IO_L18N_3_AC3") (pintype "bidirectional"))
    )
    (net (code "452") (name "unconnected-(U4D-IO_L18P_3-PadAB4)") (class "Default")
      (node (ref "U4") (pin "AB4") (pinfunction "IO_L18P_3_AB4") (pintype "bidirectional"))
    )
    (net (code "453") (name "unconnected-(U4D-IO_L19P_3-PadW9)") (class "Default")
      (node (ref "U4") (pin "W9") (pinfunction "IO_L19P_3_W9") (pintype "bidirectional"))
    )
    (net (code "454") (name "unconnected-(U4D-IO_L20N_3-PadAA3)") (class "Default")
      (node (ref "U4") (pin "AA3") (pinfunction "IO_L20N_3_AA3") (pintype "bidirectional"))
    )
    (net (code "455") (name "unconnected-(U4D-IO_L20P_3-PadAA4)") (class "Default")
      (node (ref "U4") (pin "AA4") (pinfunction "IO_L20P_3_AA4") (pintype "bidirectional"))
    )
    (net (code "456") (name "unconnected-(U4D-IO_L22P_3-PadW5)") (class "Default")
      (node (ref "U4") (pin "W5") (pinfunction "IO_L22P_3_W5") (pintype "bidirectional"))
    )
    (net (code "457") (name "unconnected-(U4D-IO_L24N_3-PadV5)") (class "Default")
      (node (ref "U4") (pin "V5") (pinfunction "IO_L24N_3_V5") (pintype "bidirectional"))
    )
    (net (code "458") (name "unconnected-(U4D-IO_L27N_3-PadT9)") (class "Default")
      (node (ref "U4") (pin "T9") (pinfunction "IO_L27N_3_T9") (pintype "bidirectional"))
    )
    (net (code "459") (name "unconnected-(U4D-IO_L27P_3-PadR10)") (class "Default")
      (node (ref "U4") (pin "R10") (pinfunction "IO_L27P_3_R10") (pintype "bidirectional"))
    )
    (net (code "460") (name "unconnected-(U4D-IO_L28N_3-PadU3)") (class "Default")
      (node (ref "U4") (pin "U3") (pinfunction "IO_L28N_3_U3") (pintype "bidirectional"))
    )
    (net (code "461") (name "unconnected-(U4D-IO_L28P_3-PadU4)") (class "Default")
      (node (ref "U4") (pin "U4") (pinfunction "IO_L28P_3_U4") (pintype "bidirectional"))
    )
    (net (code "462") (name "unconnected-(U4D-IO_L30N_3-PadT4)") (class "Default")
      (node (ref "U4") (pin "T4") (pinfunction "IO_L30N_3_T4") (pintype "bidirectional"))
    )
    (net (code "463") (name "unconnected-(U4D-IO_L30P_3-PadR5)") (class "Default")
      (node (ref "U4") (pin "R5") (pinfunction "IO_L30P_3_R5") (pintype "bidirectional"))
    )
    (net (code "464") (name "unconnected-(U4D-IO_L31N_VREF_3-PadR6)") (class "Default")
      (node (ref "U4") (pin "R6") (pinfunction "IO_L31N_VREF_3_R6") (pintype "bidirectional"))
    )
    (net (code "465") (name "unconnected-(U4D-IO_L32N_M3DQ15_3-PadAB1)") (class "Default")
      (node (ref "U4") (pin "AB1") (pinfunction "IO_L32N_M3DQ15_3_AB1") (pintype "bidirectional"))
    )
    (net (code "466") (name "unconnected-(U4D-IO_L32P_M3DQ14_3-PadAB3)") (class "Default")
      (node (ref "U4") (pin "AB3") (pinfunction "IO_L32P_M3DQ14_3_AB3") (pintype "bidirectional"))
    )
    (net (code "467") (name "unconnected-(U4D-IO_L33N_M3DQ13_3-PadAD1)") (class "Default")
      (node (ref "U4") (pin "AD1") (pinfunction "IO_L33N_M3DQ13_3_AD1") (pintype "bidirectional"))
    )
    (net (code "468") (name "unconnected-(U4D-IO_L33P_M3DQ12_3-PadAD3)") (class "Default")
      (node (ref "U4") (pin "AD3") (pinfunction "IO_L33P_M3DQ12_3_AD3") (pintype "bidirectional"))
    )
    (net (code "469") (name "unconnected-(U4D-IO_L34N_M3UDQSN_3-PadAC1)") (class "Default")
      (node (ref "U4") (pin "AC1") (pinfunction "IO_L34N_M3UDQSN_3_AC1") (pintype "bidirectional"))
    )
    (net (code "470") (name "unconnected-(U4D-IO_L34P_M3UDQS_3-PadAC2)") (class "Default")
      (node (ref "U4") (pin "AC2") (pinfunction "IO_L34P_M3UDQS_3_AC2") (pintype "bidirectional"))
    )
    (net (code "471") (name "unconnected-(U4D-IO_L35N_M3DQ11_3-PadAE1)") (class "Default")
      (node (ref "U4") (pin "AE1") (pinfunction "IO_L35N_M3DQ11_3_AE1") (pintype "bidirectional"))
    )
    (net (code "472") (name "unconnected-(U4D-IO_L35P_M3DQ10_3-PadAE2)") (class "Default")
      (node (ref "U4") (pin "AE2") (pinfunction "IO_L35P_M3DQ10_3_AE2") (pintype "bidirectional"))
    )
    (net (code "473") (name "unconnected-(U4D-IO_L36N_M3DQ9_3-PadAA1)") (class "Default")
      (node (ref "U4") (pin "AA1") (pinfunction "IO_L36N_M3DQ9_3_AA1") (pintype "bidirectional"))
    )
    (net (code "474") (name "unconnected-(U4D-IO_L36P_M3DQ8_3-PadAA2)") (class "Default")
      (node (ref "U4") (pin "AA2") (pinfunction "IO_L36P_M3DQ8_3_AA2") (pintype "bidirectional"))
    )
    (net (code "475") (name "unconnected-(U4D-IO_L37N_M3DQ1_3-PadY1)") (class "Default")
      (node (ref "U4") (pin "Y1") (pinfunction "IO_L37N_M3DQ1_3_Y1") (pintype "bidirectional"))
    )
    (net (code "476") (name "unconnected-(U4D-IO_L37P_M3DQ0_3-PadY3)") (class "Default")
      (node (ref "U4") (pin "Y3") (pinfunction "IO_L37P_M3DQ0_3_Y3") (pintype "bidirectional"))
    )
    (net (code "477") (name "unconnected-(U4D-IO_L38N_M3DQ3_3-PadW1)") (class "Default")
      (node (ref "U4") (pin "W1") (pinfunction "IO_L38N_M3DQ3_3_W1") (pintype "bidirectional"))
    )
    (net (code "478") (name "unconnected-(U4D-IO_L38P_M3DQ2_3-PadW2)") (class "Default")
      (node (ref "U4") (pin "W2") (pinfunction "IO_L38P_M3DQ2_3_W2") (pintype "bidirectional"))
    )
    (net (code "479") (name "unconnected-(U4D-IO_L39N_M3LDQSN_3-PadV1)") (class "Default")
      (node (ref "U4") (pin "V1") (pinfunction "IO_L39N_M3LDQSN_3_V1") (pintype "bidirectional"))
    )
    (net (code "480") (name "unconnected-(U4D-IO_L39P_M3LDQS_3-PadV3)") (class "Default")
      (node (ref "U4") (pin "V3") (pinfunction "IO_L39P_M3LDQS_3_V3") (pintype "bidirectional"))
    )
    (net (code "481") (name "unconnected-(U4D-IO_L40N_M3DQ7_3-PadU1)") (class "Default")
      (node (ref "U4") (pin "U1") (pinfunction "IO_L40N_M3DQ7_3_U1") (pintype "bidirectional"))
    )
    (net (code "482") (name "unconnected-(U4D-IO_L40P_M3DQ6_3-PadU2)") (class "Default")
      (node (ref "U4") (pin "U2") (pinfunction "IO_L40P_M3DQ6_3_U2") (pintype "bidirectional"))
    )
    (net (code "483") (name "unconnected-(U4D-IO_L41N_GCLK26_M3DQ5_3-PadT1)") (class "Default")
      (node (ref "U4") (pin "T1") (pinfunction "IO_L41N_GCLK26_M3DQ5_3_T1") (pintype "bidirectional"))
    )
    (net (code "484") (name "unconnected-(U4D-IO_L41P_GCLK27_M3DQ4_3-PadT3)") (class "Default")
      (node (ref "U4") (pin "T3") (pinfunction "IO_L41P_GCLK27_M3DQ4_3_T3") (pintype "bidirectional"))
    )
    (net (code "485") (name "unconnected-(U4D-IO_L42N_GCLK24_M3LDM_3-PadW3)") (class "Default")
      (node (ref "U4") (pin "W3") (pinfunction "IO_L42N_GCLK24_M3LDM_3_W3") (pintype "bidirectional"))
    )
    (net (code "486") (name "unconnected-(U4D-IO_L42P_GCLK25_TRDY2_M3UDM_3-PadV4)") (class "Default")
      (node (ref "U4") (pin "V4") (pinfunction "IO_L42P_GCLK25_TRDY2_M3UDM_3_V4") (pintype "bidirectional"))
    )
    (net (code "487") (name "unconnected-(U4D-IO_L48N_M3BA1_3-PadP1)") (class "Default")
      (node (ref "U4") (pin "P1") (pinfunction "IO_L48N_M3BA1_3_P1") (pintype "bidirectional"))
    )
    (net (code "488") (name "unconnected-(U4D-IO_L48P_M3BA0_3-PadP3)") (class "Default")
      (node (ref "U4") (pin "P3") (pinfunction "IO_L48P_M3BA0_3_P3") (pintype "bidirectional"))
    )
    (net (code "489") (name "unconnected-(U4D-IO_L50N_M3BA2_3-PadN5)") (class "Default")
      (node (ref "U4") (pin "N5") (pinfunction "IO_L50N_M3BA2_3_N5") (pintype "bidirectional"))
    )
    (net (code "490") (name "unconnected-(U4D-IO_L50P_M3WE_3-PadP5)") (class "Default")
      (node (ref "U4") (pin "P5") (pinfunction "IO_L50P_M3WE_3_P5") (pintype "bidirectional"))
    )
    (net (code "491") (name "unconnected-(U4D-IO_L51N_M3A4_3-PadN9)") (class "Default")
      (node (ref "U4") (pin "N9") (pinfunction "IO_L51N_M3A4_3_N9") (pintype "bidirectional"))
    )
    (net (code "492") (name "unconnected-(U4D-IO_L52N_M3A9_3-PadN3)") (class "Default")
      (node (ref "U4") (pin "N3") (pinfunction "IO_L52N_M3A9_3_N3") (pintype "bidirectional"))
    )
    (net (code "493") (name "unconnected-(U4D-IO_L52P_M3A8_3-PadN4)") (class "Default")
      (node (ref "U4") (pin "N4") (pinfunction "IO_L52P_M3A8_3_N4") (pintype "bidirectional"))
    )
    (net (code "494") (name "unconnected-(U4D-IO_L53P_M3CKE_3-PadM9)") (class "Default")
      (node (ref "U4") (pin "M9") (pinfunction "IO_L53P_M3CKE_3_M9") (pintype "bidirectional"))
    )
    (net (code "495") (name "unconnected-(U4D-IO_L55N_M3A14_3-PadM4)") (class "Default")
      (node (ref "U4") (pin "M4") (pinfunction "IO_L55N_M3A14_3_M4") (pintype "bidirectional"))
    )
    (net (code "496") (name "unconnected-(U4F-IO_L3N_M5A11_5-PadC24)") (class "Default")
      (node (ref "U4") (pin "C24") (pinfunction "IO_L3N_M5A11_5_C24") (pintype "bidirectional"))
    )
    (net (code "497") (name "unconnected-(U4F-IO_L3P_M5RESET_5-PadD23)") (class "Default")
      (node (ref "U4") (pin "D23") (pinfunction "IO_L3P_M5RESET_5_D23") (pintype "bidirectional"))
    )
    (net (code "498") (name "unconnected-(U4F-IO_L4N_M5A12_5-PadD22)") (class "Default")
      (node (ref "U4") (pin "D22") (pinfunction "IO_L4N_M5A12_5_D22") (pintype "bidirectional"))
    )
    (net (code "499") (name "unconnected-(U4F-IO_L4P_M5CKE_5-PadF22)") (class "Default")
      (node (ref "U4") (pin "F22") (pinfunction "IO_L4P_M5CKE_5_F22") (pintype "bidirectional"))
    )
    (net (code "500") (name "unconnected-(U4F-IO_L5N_M5A9_5-PadH21)") (class "Default")
      (node (ref "U4") (pin "H21") (pinfunction "IO_L5N_M5A9_5_H21") (pintype "bidirectional"))
    )
    (net (code "501") (name "unconnected-(U4F-IO_L5P_M5A8_5-PadH20)") (class "Default")
      (node (ref "U4") (pin "H20") (pinfunction "IO_L5P_M5A8_5_H20") (pintype "bidirectional"))
    )
    (net (code "502") (name "unconnected-(U4F-IO_L6N_M5A4_5-PadG22)") (class "Default")
      (node (ref "U4") (pin "G22") (pinfunction "IO_L6N_M5A4_5_G22") (pintype "bidirectional"))
    )
    (net (code "503") (name "unconnected-(U4F-IO_L6P_M5A10_5-PadH22)") (class "Default")
      (node (ref "U4") (pin "H22") (pinfunction "IO_L6P_M5A10_5_H22") (pintype "bidirectional"))
    )
    (net (code "504") (name "unconnected-(U4F-IO_L7N_M5BA2_5-PadE24)") (class "Default")
      (node (ref "U4") (pin "E24") (pinfunction "IO_L7N_M5BA2_5_E24") (pintype "bidirectional"))
    )
    (net (code "505") (name "unconnected-(U4F-IO_L7P_M5WE_5-PadE23)") (class "Default")
      (node (ref "U4") (pin "E23") (pinfunction "IO_L7P_M5WE_5_E23") (pintype "bidirectional"))
    )
    (net (code "506") (name "unconnected-(U4F-IO_L8N_M5A2_5-PadG24)") (class "Default")
      (node (ref "U4") (pin "G24") (pinfunction "IO_L8N_M5A2_5_G24") (pintype "bidirectional"))
    )
    (net (code "507") (name "unconnected-(U4F-IO_L8P_M5A7_5-PadG23)") (class "Default")
      (node (ref "U4") (pin "G23") (pinfunction "IO_L8P_M5A7_5_G23") (pintype "bidirectional"))
    )
    (net (code "508") (name "unconnected-(U4F-IO_L9N_M5BA1_5-PadG19)") (class "Default")
      (node (ref "U4") (pin "G19") (pinfunction "IO_L9N_M5BA1_5_G19") (pintype "bidirectional"))
    )
    (net (code "509") (name "unconnected-(U4F-IO_L9P_M5BA0_5-PadH18)") (class "Default")
      (node (ref "U4") (pin "H18") (pinfunction "IO_L9P_M5BA0_5_H18") (pintype "bidirectional"))
    )
    (net (code "510") (name "unconnected-(U4F-IO_L10N_M5A1_5-PadA25)") (class "Default")
      (node (ref "U4") (pin "A25") (pinfunction "IO_L10N_M5A1_5_A25") (pintype "bidirectional"))
    )
    (net (code "511") (name "unconnected-(U4F-IO_L10P_M5A0_5-PadB24)") (class "Default")
      (node (ref "U4") (pin "B24") (pinfunction "IO_L10P_M5A0_5_B24") (pintype "bidirectional"))
    )
    (net (code "512") (name "unconnected-(U4F-IO_L11N_M5CLKN_5-PadC26)") (class "Default")
      (node (ref "U4") (pin "C26") (pinfunction "IO_L11N_M5CLKN_5_C26") (pintype "bidirectional"))
    )
    (net (code "513") (name "unconnected-(U4F-IO_L12N_M5ODT_5-PadB26)") (class "Default")
      (node (ref "U4") (pin "B26") (pinfunction "IO_L12N_M5ODT_5_B26") (pintype "bidirectional"))
    )
    (net (code "514") (name "unconnected-(U4F-IO_L12P_M5A3_5-PadB25)") (class "Default")
      (node (ref "U4") (pin "B25") (pinfunction "IO_L12P_M5A3_5_B25") (pintype "bidirectional"))
    )
    (net (code "515") (name "unconnected-(U4F-IO_L13N_M5A6_5-PadK21)") (class "Default")
      (node (ref "U4") (pin "K21") (pinfunction "IO_L13N_M5A6_5_K21") (pintype "bidirectional"))
    )
    (net (code "516") (name "unconnected-(U4F-IO_L13P_M5A5_5-PadK20)") (class "Default")
      (node (ref "U4") (pin "K20") (pinfunction "IO_L13P_M5A5_5_K20") (pintype "bidirectional"))
    )
    (net (code "517") (name "unconnected-(U4F-IO_L14N_M5CASN_5-PadJ22)") (class "Default")
      (node (ref "U4") (pin "J22") (pinfunction "IO_L14N_M5CASN_5_J22") (pintype "bidirectional"))
    )
    (net (code "518") (name "unconnected-(U4F-IO_L14P_M5RASN_5-PadK22)") (class "Default")
      (node (ref "U4") (pin "K22") (pinfunction "IO_L14P_M5RASN_5_K22") (pintype "bidirectional"))
    )
    (net (code "519") (name "unconnected-(U4F-IO_L15N_M5LDM_5-PadJ24)") (class "Default")
      (node (ref "U4") (pin "J24") (pinfunction "IO_L15N_M5LDM_5_J24") (pintype "bidirectional"))
    )
    (net (code "520") (name "unconnected-(U4F-IO_L15P_M5UDM_5-PadJ23)") (class "Default")
      (node (ref "U4") (pin "J23") (pinfunction "IO_L15P_M5UDM_5_J23") (pintype "bidirectional"))
    )
    (net (code "521") (name "unconnected-(U4F-IO_L16N_M5DQ5_5-PadE26)") (class "Default")
      (node (ref "U4") (pin "E26") (pinfunction "IO_L16N_M5DQ5_5_E26") (pintype "bidirectional"))
    )
    (net (code "522") (name "unconnected-(U4F-IO_L16P_M5DQ4_5-PadE25)") (class "Default")
      (node (ref "U4") (pin "E25") (pinfunction "IO_L16P_M5DQ4_5_E25") (pintype "bidirectional"))
    )
    (net (code "523") (name "unconnected-(U4F-IO_L17N_M5DQ7_5-PadD26)") (class "Default")
      (node (ref "U4") (pin "D26") (pinfunction "IO_L17N_M5DQ7_5_D26") (pintype "bidirectional"))
    )
    (net (code "524") (name "unconnected-(U4F-IO_L17P_M5DQ6_5-PadD24)") (class "Default")
      (node (ref "U4") (pin "D24") (pinfunction "IO_L17P_M5DQ6_5_D24") (pintype "bidirectional"))
    )
    (net (code "525") (name "unconnected-(U4F-IO_L18N_M5LDQSN_5-PadF26)") (class "Default")
      (node (ref "U4") (pin "F26") (pinfunction "IO_L18N_M5LDQSN_5_F26") (pintype "bidirectional"))
    )
    (net (code "526") (name "unconnected-(U4F-IO_L18P_M5LDQS_5-PadF24)") (class "Default")
      (node (ref "U4") (pin "F24") (pinfunction "IO_L18P_M5LDQS_5_F24") (pintype "bidirectional"))
    )
    (net (code "527") (name "unconnected-(U4F-IO_L19N_M5DQ3_5-PadH26)") (class "Default")
      (node (ref "U4") (pin "H26") (pinfunction "IO_L19N_M5DQ3_5_H26") (pintype "bidirectional"))
    )
    (net (code "528") (name "unconnected-(U4F-IO_L19P_M5DQ2_5-PadH24)") (class "Default")
      (node (ref "U4") (pin "H24") (pinfunction "IO_L19P_M5DQ2_5_H24") (pintype "bidirectional"))
    )
    (net (code "529") (name "unconnected-(U4F-IO_L20N_M5DQ1_5-PadG26)") (class "Default")
      (node (ref "U4") (pin "G26") (pinfunction "IO_L20N_M5DQ1_5_G26") (pintype "bidirectional"))
    )
    (net (code "530") (name "unconnected-(U4F-IO_L20P_M5DQ0_5-PadG25)") (class "Default")
      (node (ref "U4") (pin "G25") (pinfunction "IO_L20P_M5DQ0_5_G25") (pintype "bidirectional"))
    )
    (net (code "531") (name "unconnected-(U4F-IO_L21N_M5DQ9_5-PadK26)") (class "Default")
      (node (ref "U4") (pin "K26") (pinfunction "IO_L21N_M5DQ9_5_K26") (pintype "bidirectional"))
    )
    (net (code "532") (name "unconnected-(U4F-IO_L21P_M5DQ8_5-PadK24)") (class "Default")
      (node (ref "U4") (pin "K24") (pinfunction "IO_L21P_M5DQ8_5_K24") (pintype "bidirectional"))
    )
    (net (code "533") (name "unconnected-(U4F-IO_L22N_M5DQ11_5-PadJ26)") (class "Default")
      (node (ref "U4") (pin "J26") (pinfunction "IO_L22N_M5DQ11_5_J26") (pintype "bidirectional"))
    )
    (net (code "534") (name "unconnected-(U4F-IO_L22P_M5DQ10_5-PadJ25)") (class "Default")
      (node (ref "U4") (pin "J25") (pinfunction "IO_L22P_M5DQ10_5_J25") (pintype "bidirectional"))
    )
    (net (code "535") (name "unconnected-(U4F-IO_L23N_M5UDQSN_5-PadM26)") (class "Default")
      (node (ref "U4") (pin "M26") (pinfunction "IO_L23N_M5UDQSN_5_M26") (pintype "bidirectional"))
    )
    (net (code "536") (name "unconnected-(U4F-IO_L23P_M5UDQS_5-PadM24)") (class "Default")
      (node (ref "U4") (pin "M24") (pinfunction "IO_L23P_M5UDQS_5_M24") (pintype "bidirectional"))
    )
    (net (code "537") (name "unconnected-(U4F-IO_L24N_M5DQ13_5-PadL26)") (class "Default")
      (node (ref "U4") (pin "L26") (pinfunction "IO_L24N_M5DQ13_5_L26") (pintype "bidirectional"))
    )
    (net (code "538") (name "unconnected-(U4F-IO_L24P_M5DQ12_5-PadL25)") (class "Default")
      (node (ref "U4") (pin "L25") (pinfunction "IO_L24P_M5DQ12_5_L25") (pintype "bidirectional"))
    )
    (net (code "539") (name "unconnected-(U4F-IO_L25N_M5DQ15_5-PadN26)") (class "Default")
      (node (ref "U4") (pin "N26") (pinfunction "IO_L25N_M5DQ15_5_N26") (pintype "bidirectional"))
    )
    (net (code "540") (name "unconnected-(U4F-IO_L25P_M5DQ14_5-PadN25)") (class "Default")
      (node (ref "U4") (pin "N25") (pinfunction "IO_L25P_M5DQ14_5_N25") (pintype "bidirectional"))
    )
    (net (code "541") (name "unconnected-(U4F-IO_L26N_VREF_5-PadL21)") (class "Default")
      (node (ref "U4") (pin "L21") (pinfunction "IO_L26N_VREF_5_L21") (pintype "bidirectional"))
    )
    (net (code "542") (name "unconnected-(U4F-IO_L26P_5-PadL20)") (class "Default")
      (node (ref "U4") (pin "L20") (pinfunction "IO_L26P_5_L20") (pintype "bidirectional"))
    )
    (net (code "543") (name "unconnected-(U4F-IO_L27N_5-PadJ20)") (class "Default")
      (node (ref "U4") (pin "J20") (pinfunction "IO_L27N_5_J20") (pintype "bidirectional"))
    )
    (net (code "544") (name "unconnected-(U4F-IO_L27P_5-PadH19)") (class "Default")
      (node (ref "U4") (pin "H19") (pinfunction "IO_L27P_5_H19") (pintype "bidirectional"))
    )
  )
)
